# r-2r.net
KiCad netlist of a schematic drawn in EAGLE
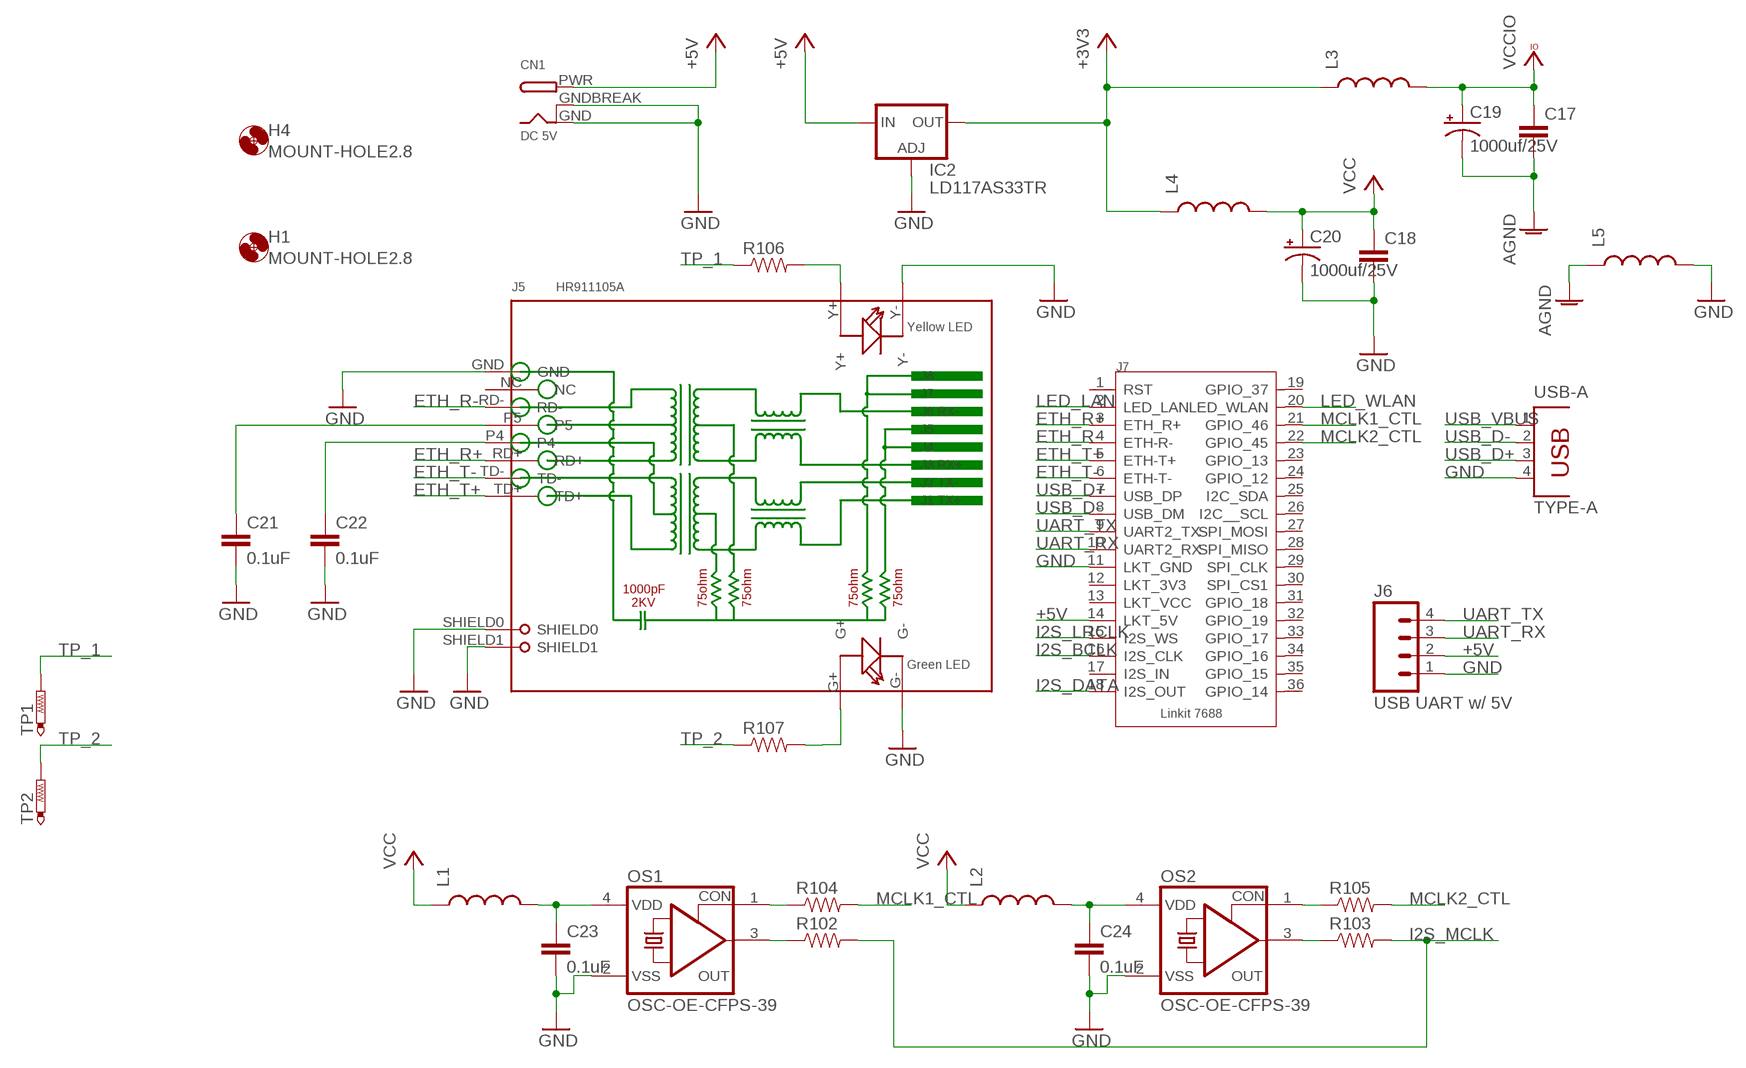
[diagram p0: schematic, sheet 1]
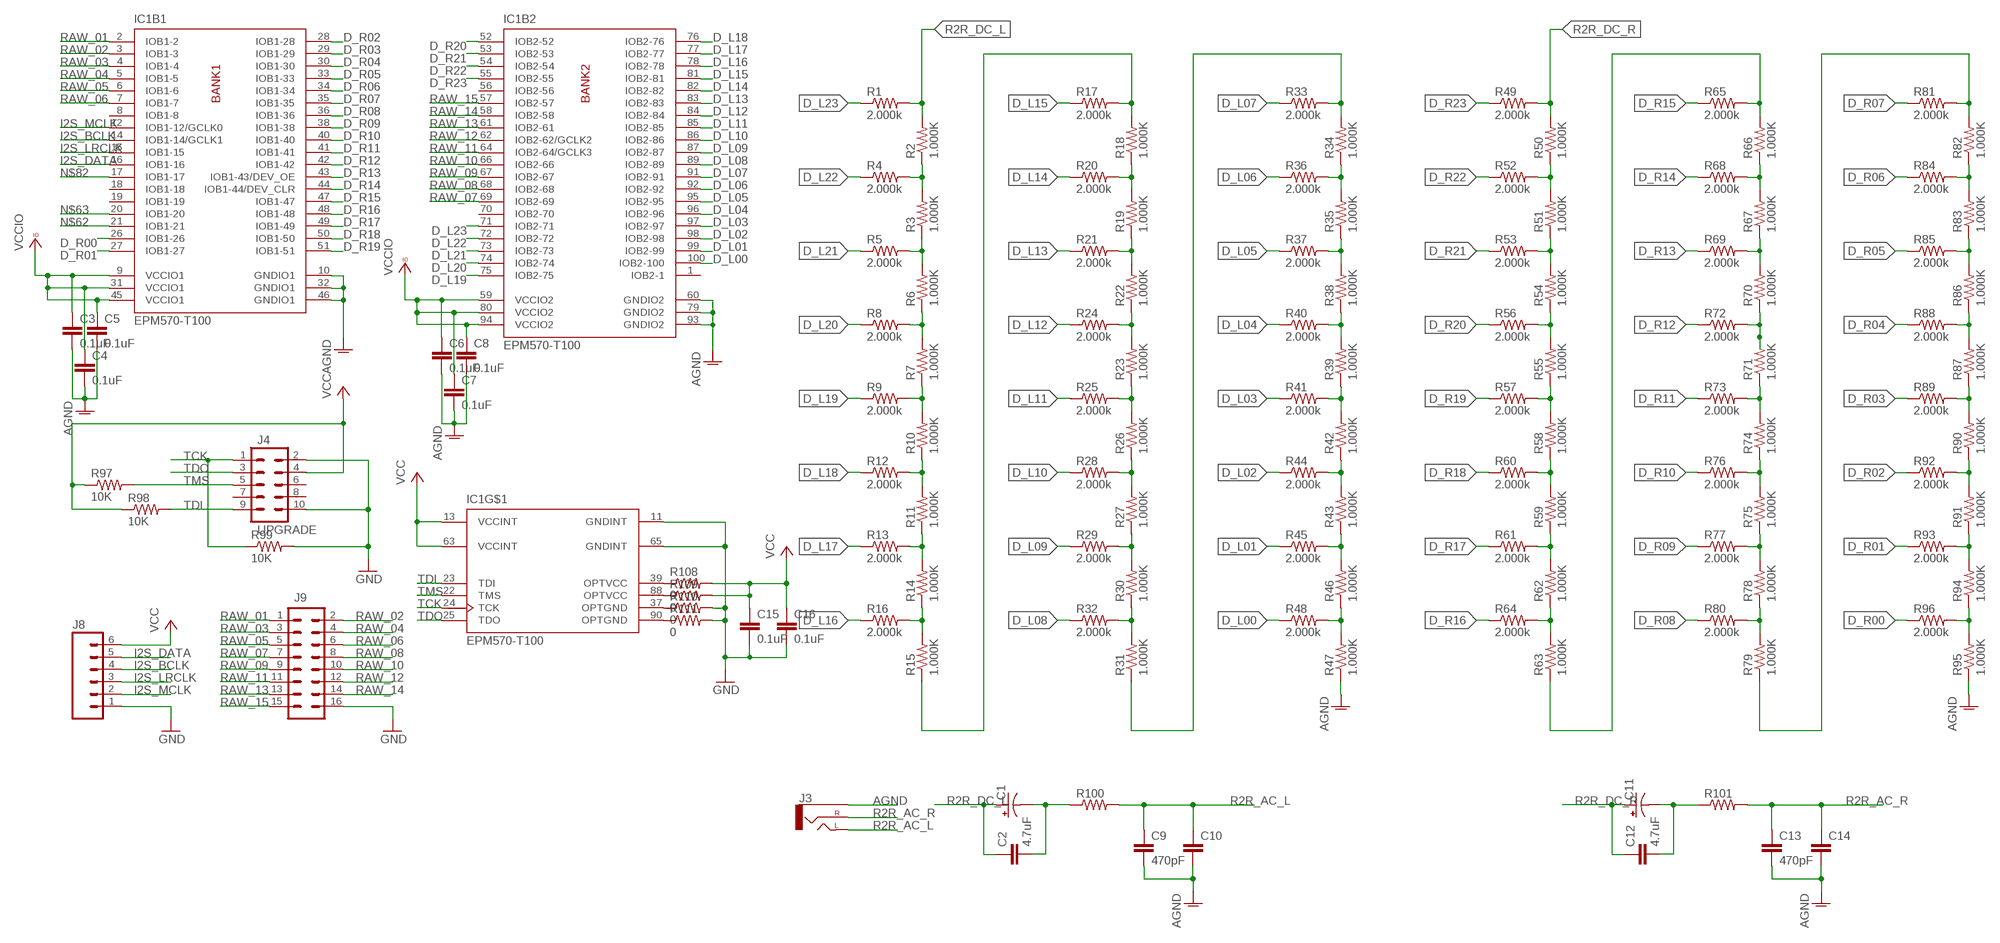
[diagram p1: schematic, sheet 2]

(export (version "E")
  (design (tool "Eeschema 10.0.6"))
  (components
    (comp (ref "C1")
      (value "10UF-25V-20%(PTH)KIT")
      (footprint "eagle-import:CPOL-RADIAL-10UF-25V-KIT")
      (libsource (lib "eagle-import") (part "10UF-25V-20%(PTH)KIT"))
    )
    (comp (ref "C2")
      (value "4.7uF")
      (footprint "eagle-import:1206-CAP")
      (libsource (lib "eagle-import") (part "4.7UF-16V-20%,+80%-(1206)"))
    )
    (comp (ref "C3")
      (value "0.1uF")
      (footprint "eagle-import:0603-CAP")
      (libsource (lib "eagle-import") (part "0.1UF-25V(+80/-20%)(0603)"))
    )
    (comp (ref "C4")
      (value "0.1uF")
      (footprint "eagle-import:0603-CAP")
      (libsource (lib "eagle-import") (part "0.1UF-25V(+80/-20%)(0603)"))
    )
    (comp (ref "C5")
      (value "0.1uF")
      (footprint "eagle-import:0603-CAP")
      (libsource (lib "eagle-import") (part "0.1UF-25V(+80/-20%)(0603)"))
    )
    (comp (ref "C6")
      (value "0.1uF")
      (footprint "eagle-import:0603-CAP")
      (libsource (lib "eagle-import") (part "0.1UF-25V(+80/-20%)(0603)"))
    )
    (comp (ref "C7")
      (value "0.1uF")
      (footprint "eagle-import:0603-CAP")
      (libsource (lib "eagle-import") (part "0.1UF-25V(+80/-20%)(0603)"))
    )
    (comp (ref "C8")
      (value "0.1uF")
      (footprint "eagle-import:0603-CAP")
      (libsource (lib "eagle-import") (part "0.1UF-25V(+80/-20%)(0603)"))
    )
    (comp (ref "C9")
      (value "470pF")
      (footprint "eagle-import:0603-CAP")
      (libsource (lib "eagle-import") (part "470PF-50V-5%(0603)SMD"))
    )
    (comp (ref "C10")
      (value "CAPPTH1")
      (footprint "eagle-import:CAP-PTH-5MM")
      (libsource (lib "eagle-import") (part "CAPPTH1"))
    )
    (comp (ref "C11")
      (value "10UF-25V-20%(PTH)KIT")
      (footprint "eagle-import:CPOL-RADIAL-10UF-25V-KIT")
      (libsource (lib "eagle-import") (part "10UF-25V-20%(PTH)KIT"))
    )
    (comp (ref "C12")
      (value "4.7uF")
      (footprint "eagle-import:1206-CAP")
      (libsource (lib "eagle-import") (part "4.7UF-16V-20%,+80%-(1206)"))
    )
    (comp (ref "C13")
      (value "470pF")
      (footprint "eagle-import:0603-CAP")
      (libsource (lib "eagle-import") (part "470PF-50V-5%(0603)SMD"))
    )
    (comp (ref "C14")
      (value "CAPPTH1")
      (footprint "eagle-import:CAP-PTH-5MM")
      (libsource (lib "eagle-import") (part "CAPPTH1"))
    )
    (comp (ref "C15")
      (value "0.1uF")
      (footprint "eagle-import:0603-CAP")
      (libsource (lib "eagle-import") (part "0.1UF-25V(+80/-20%)(0603)"))
    )
    (comp (ref "C16")
      (value "0.1uF")
      (footprint "eagle-import:0603-CAP")
      (libsource (lib "eagle-import") (part "0.1UF-25V(+80/-20%)(0603)"))
    )
    (comp (ref "IC1")
      (value "EPM570-T100")
      (footprint "eagle-import:TQFP100")
      (libsource (lib "eagle-import") (part "EPM570-T100"))
    )
    (comp (ref "J3")
      (value "AUDIO-JACKSMD2")
      (footprint "eagle-import:AUDIO-JACK-3.5MM-SMD")
      (libsource (lib "eagle-import") (part "AUDIO-JACKSMD2"))
    )
    (comp (ref "J4")
      (value "UPGRADE")
      (footprint "eagle-import:2X5-SHROUDED")
      (libsource (lib "eagle-import") (part "M05X2SHD"))
    )
    (comp (ref "J8")
      (value "M06SILK_FEMALE_PTH")
      (footprint "eagle-import:1X06")
      (libsource (lib "eagle-import") (part "M06SILK_FEMALE_PTH"))
    )
    (comp (ref "J9")
      (value "M08X2")
      (footprint "eagle-import:2X8")
      (libsource (lib "eagle-import") (part "M08X2"))
    )
    (comp (ref "R1")
      (value "2.000k")
      (footprint "eagle-import:0603-RES")
      (libsource (lib "eagle-import") (part "2.0KOHM1/10W5%(0603)"))
    )
    (comp (ref "R2")
      (value "1.000K")
      (footprint "eagle-import:0603-RES")
      (libsource (lib "eagle-import") (part "1KOHM-1/10W-1%(0603)"))
    )
    (comp (ref "R3")
      (value "1.000K")
      (footprint "eagle-import:0603-RES")
      (libsource (lib "eagle-import") (part "1KOHM-1/10W-1%(0603)"))
    )
    (comp (ref "R4")
      (value "2.000k")
      (footprint "eagle-import:0603-RES")
      (libsource (lib "eagle-import") (part "2.0KOHM1/10W5%(0603)"))
    )
    (comp (ref "R5")
      (value "2.000k")
      (footprint "eagle-import:0603-RES")
      (libsource (lib "eagle-import") (part "2.0KOHM1/10W5%(0603)"))
    )
    (comp (ref "R6")
      (value "1.000K")
      (footprint "eagle-import:0603-RES")
      (libsource (lib "eagle-import") (part "1KOHM-1/10W-1%(0603)"))
    )
    (comp (ref "R7")
      (value "1.000K")
      (footprint "eagle-import:0603-RES")
      (libsource (lib "eagle-import") (part "1KOHM-1/10W-1%(0603)"))
    )
    (comp (ref "R8")
      (value "2.000k")
      (footprint "eagle-import:0603-RES")
      (libsource (lib "eagle-import") (part "2.0KOHM1/10W5%(0603)"))
    )
    (comp (ref "R9")
      (value "2.000k")
      (footprint "eagle-import:0603-RES")
      (libsource (lib "eagle-import") (part "2.0KOHM1/10W5%(0603)"))
    )
    (comp (ref "R10")
      (value "1.000K")
      (footprint "eagle-import:0603-RES")
      (libsource (lib "eagle-import") (part "1KOHM-1/10W-1%(0603)"))
    )
    (comp (ref "R11")
      (value "1.000K")
      (footprint "eagle-import:0603-RES")
      (libsource (lib "eagle-import") (part "1KOHM-1/10W-1%(0603)"))
    )
    (comp (ref "R12")
      (value "2.000k")
      (footprint "eagle-import:0603-RES")
      (libsource (lib "eagle-import") (part "2.0KOHM1/10W5%(0603)"))
    )
    (comp (ref "R13")
      (value "2.000k")
      (footprint "eagle-import:0603-RES")
      (libsource (lib "eagle-import") (part "2.0KOHM1/10W5%(0603)"))
    )
    (comp (ref "R14")
      (value "1.000K")
      (footprint "eagle-import:0603-RES")
      (libsource (lib "eagle-import") (part "1KOHM-1/10W-1%(0603)"))
    )
    (comp (ref "R15")
      (value "1.000K")
      (footprint "eagle-import:0603-RES")
      (libsource (lib "eagle-import") (part "1KOHM-1/10W-1%(0603)"))
    )
    (comp (ref "R16")
      (value "2.000k")
      (footprint "eagle-import:0603-RES")
      (libsource (lib "eagle-import") (part "2.0KOHM1/10W5%(0603)"))
    )
    (comp (ref "R17")
      (value "2.000k")
      (footprint "eagle-import:0603-RES")
      (libsource (lib "eagle-import") (part "2.0KOHM1/10W5%(0603)"))
    )
    (comp (ref "R18")
      (value "1.000K")
      (footprint "eagle-import:0603-RES")
      (libsource (lib "eagle-import") (part "1KOHM-1/10W-1%(0603)"))
    )
    (comp (ref "R19")
      (value "1.000K")
      (footprint "eagle-import:0603-RES")
      (libsource (lib "eagle-import") (part "1KOHM-1/10W-1%(0603)"))
    )
    (comp (ref "R20")
      (value "2.000k")
      (footprint "eagle-import:0603-RES")
      (libsource (lib "eagle-import") (part "2.0KOHM1/10W5%(0603)"))
    )
    (comp (ref "R21")
      (value "2.000k")
      (footprint "eagle-import:0603-RES")
      (libsource (lib "eagle-import") (part "2.0KOHM1/10W5%(0603)"))
    )
    (comp (ref "R22")
      (value "1.000K")
      (footprint "eagle-import:0603-RES")
      (libsource (lib "eagle-import") (part "1KOHM-1/10W-1%(0603)"))
    )
    (comp (ref "R23")
      (value "1.000K")
      (footprint "eagle-import:0603-RES")
      (libsource (lib "eagle-import") (part "1KOHM-1/10W-1%(0603)"))
    )
    (comp (ref "R24")
      (value "2.000k")
      (footprint "eagle-import:0603-RES")
      (libsource (lib "eagle-import") (part "2.0KOHM1/10W5%(0603)"))
    )
    (comp (ref "R25")
      (value "2.000k")
      (footprint "eagle-import:0603-RES")
      (libsource (lib "eagle-import") (part "2.0KOHM1/10W5%(0603)"))
    )
    (comp (ref "R26")
      (value "1.000K")
      (footprint "eagle-import:0603-RES")
      (libsource (lib "eagle-import") (part "1KOHM-1/10W-1%(0603)"))
    )
    (comp (ref "R27")
      (value "1.000K")
      (footprint "eagle-import:0603-RES")
      (libsource (lib "eagle-import") (part "1KOHM-1/10W-1%(0603)"))
    )
    (comp (ref "R28")
      (value "2.000k")
      (footprint "eagle-import:0603-RES")
      (libsource (lib "eagle-import") (part "2.0KOHM1/10W5%(0603)"))
    )
    (comp (ref "R29")
      (value "2.000k")
      (footprint "eagle-import:0603-RES")
      (libsource (lib "eagle-import") (part "2.0KOHM1/10W5%(0603)"))
    )
    (comp (ref "R30")
      (value "1.000K")
      (footprint "eagle-import:0603-RES")
      (libsource (lib "eagle-import") (part "1KOHM-1/10W-1%(0603)"))
    )
    (comp (ref "R31")
      (value "1.000K")
      (footprint "eagle-import:0603-RES")
      (libsource (lib "eagle-import") (part "1KOHM-1/10W-1%(0603)"))
    )
    (comp (ref "R32")
      (value "2.000k")
      (footprint "eagle-import:0603-RES")
      (libsource (lib "eagle-import") (part "2.0KOHM1/10W5%(0603)"))
    )
    (comp (ref "R33")
      (value "2.000k")
      (footprint "eagle-import:0603-RES")
      (libsource (lib "eagle-import") (part "2.0KOHM1/10W5%(0603)"))
    )
    (comp (ref "R34")
      (value "1.000K")
      (footprint "eagle-import:0603-RES")
      (libsource (lib "eagle-import") (part "1KOHM-1/10W-1%(0603)"))
    )
    (comp (ref "R35")
      (value "1.000K")
      (footprint "eagle-import:0603-RES")
      (libsource (lib "eagle-import") (part "1KOHM-1/10W-1%(0603)"))
    )
    (comp (ref "R36")
      (value "2.000k")
      (footprint "eagle-import:0603-RES")
      (libsource (lib "eagle-import") (part "2.0KOHM1/10W5%(0603)"))
    )
    (comp (ref "R37")
      (value "2.000k")
      (footprint "eagle-import:0603-RES")
      (libsource (lib "eagle-import") (part "2.0KOHM1/10W5%(0603)"))
    )
    (comp (ref "R38")
      (value "1.000K")
      (footprint "eagle-import:0603-RES")
      (libsource (lib "eagle-import") (part "1KOHM-1/10W-1%(0603)"))
    )
    (comp (ref "R39")
      (value "1.000K")
      (footprint "eagle-import:0603-RES")
      (libsource (lib "eagle-import") (part "1KOHM-1/10W-1%(0603)"))
    )
    (comp (ref "R40")
      (value "2.000k")
      (footprint "eagle-import:0603-RES")
      (libsource (lib "eagle-import") (part "2.0KOHM1/10W5%(0603)"))
    )
    (comp (ref "R41")
      (value "2.000k")
      (footprint "eagle-import:0603-RES")
      (libsource (lib "eagle-import") (part "2.0KOHM1/10W5%(0603)"))
    )
    (comp (ref "R42")
      (value "1.000K")
      (footprint "eagle-import:0603-RES")
      (libsource (lib "eagle-import") (part "1KOHM-1/10W-1%(0603)"))
    )
    (comp (ref "R43")
      (value "1.000K")
      (footprint "eagle-import:0603-RES")
      (libsource (lib "eagle-import") (part "1KOHM-1/10W-1%(0603)"))
    )
    (comp (ref "R44")
      (value "2.000k")
      (footprint "eagle-import:0603-RES")
      (libsource (lib "eagle-import") (part "2.0KOHM1/10W5%(0603)"))
    )
    (comp (ref "R45")
      (value "2.000k")
      (footprint "eagle-import:0603-RES")
      (libsource (lib "eagle-import") (part "2.0KOHM1/10W5%(0603)"))
    )
    (comp (ref "R46")
      (value "1.000K")
      (footprint "eagle-import:0603-RES")
      (libsource (lib "eagle-import") (part "1KOHM-1/10W-1%(0603)"))
    )
    (comp (ref "R47")
      (value "1.000K")
      (footprint "eagle-import:0603-RES")
      (libsource (lib "eagle-import") (part "1KOHM-1/10W-1%(0603)"))
    )
    (comp (ref "R48")
      (value "2.000k")
      (footprint "eagle-import:0603-RES")
      (libsource (lib "eagle-import") (part "2.0KOHM1/10W5%(0603)"))
    )
    (comp (ref "R49")
      (value "2.000k")
      (footprint "eagle-import:0603-RES")
      (libsource (lib "eagle-import") (part "2.0KOHM1/10W5%(0603)"))
    )
    (comp (ref "R50")
      (value "1.000K")
      (footprint "eagle-import:0603-RES")
      (libsource (lib "eagle-import") (part "1KOHM-1/10W-1%(0603)"))
    )
    (comp (ref "R51")
      (value "1.000K")
      (footprint "eagle-import:0603-RES")
      (libsource (lib "eagle-import") (part "1KOHM-1/10W-1%(0603)"))
    )
    (comp (ref "R52")
      (value "2.000k")
      (footprint "eagle-import:0603-RES")
      (libsource (lib "eagle-import") (part "2.0KOHM1/10W5%(0603)"))
    )
    (comp (ref "R53")
      (value "2.000k")
      (footprint "eagle-import:0603-RES")
      (libsource (lib "eagle-import") (part "2.0KOHM1/10W5%(0603)"))
    )
    (comp (ref "R54")
      (value "1.000K")
      (footprint "eagle-import:0603-RES")
      (libsource (lib "eagle-import") (part "1KOHM-1/10W-1%(0603)"))
    )
    (comp (ref "R55")
      (value "1.000K")
      (footprint "eagle-import:0603-RES")
      (libsource (lib "eagle-import") (part "1KOHM-1/10W-1%(0603)"))
    )
    (comp (ref "R56")
      (value "2.000k")
      (footprint "eagle-import:0603-RES")
      (libsource (lib "eagle-import") (part "2.0KOHM1/10W5%(0603)"))
    )
    (comp (ref "R57")
      (value "2.000k")
      (footprint "eagle-import:0603-RES")
      (libsource (lib "eagle-import") (part "2.0KOHM1/10W5%(0603)"))
    )
    (comp (ref "R58")
      (value "1.000K")
      (footprint "eagle-import:0603-RES")
      (libsource (lib "eagle-import") (part "1KOHM-1/10W-1%(0603)"))
    )
    (comp (ref "R59")
      (value "1.000K")
      (footprint "eagle-import:0603-RES")
      (libsource (lib "eagle-import") (part "1KOHM-1/10W-1%(0603)"))
    )
    (comp (ref "R60")
      (value "2.000k")
      (footprint "eagle-import:0603-RES")
      (libsource (lib "eagle-import") (part "2.0KOHM1/10W5%(0603)"))
    )
    (comp (ref "R61")
      (value "2.000k")
      (footprint "eagle-import:0603-RES")
      (libsource (lib "eagle-import") (part "2.0KOHM1/10W5%(0603)"))
    )
    (comp (ref "R62")
      (value "1.000K")
      (footprint "eagle-import:0603-RES")
      (libsource (lib "eagle-import") (part "1KOHM-1/10W-1%(0603)"))
    )
    (comp (ref "R63")
      (value "1.000K")
      (footprint "eagle-import:0603-RES")
      (libsource (lib "eagle-import") (part "1KOHM-1/10W-1%(0603)"))
    )
    (comp (ref "R64")
      (value "2.000k")
      (footprint "eagle-import:0603-RES")
      (libsource (lib "eagle-import") (part "2.0KOHM1/10W5%(0603)"))
    )
    (comp (ref "R65")
      (value "2.000k")
      (footprint "eagle-import:0603-RES")
      (libsource (lib "eagle-import") (part "2.0KOHM1/10W5%(0603)"))
    )
    (comp (ref "R66")
      (value "1.000K")
      (footprint "eagle-import:0603-RES")
      (libsource (lib "eagle-import") (part "1KOHM-1/10W-1%(0603)"))
    )
    (comp (ref "R67")
      (value "1.000K")
      (footprint "eagle-import:0603-RES")
      (libsource (lib "eagle-import") (part "1KOHM-1/10W-1%(0603)"))
    )
    (comp (ref "R68")
      (value "2.000k")
      (footprint "eagle-import:0603-RES")
      (libsource (lib "eagle-import") (part "2.0KOHM1/10W5%(0603)"))
    )
    (comp (ref "R69")
      (value "2.000k")
      (footprint "eagle-import:0603-RES")
      (libsource (lib "eagle-import") (part "2.0KOHM1/10W5%(0603)"))
    )
    (comp (ref "R70")
      (value "1.000K")
      (footprint "eagle-import:0603-RES")
      (libsource (lib "eagle-import") (part "1KOHM-1/10W-1%(0603)"))
    )
    (comp (ref "R71")
      (value "1.000K")
      (footprint "eagle-import:0603-RES")
      (libsource (lib "eagle-import") (part "1KOHM-1/10W-1%(0603)"))
    )
    (comp (ref "R72")
      (value "2.000k")
      (footprint "eagle-import:0603-RES")
      (libsource (lib "eagle-import") (part "2.0KOHM1/10W5%(0603)"))
    )
    (comp (ref "R73")
      (value "2.000k")
      (footprint "eagle-import:0603-RES")
      (libsource (lib "eagle-import") (part "2.0KOHM1/10W5%(0603)"))
    )
    (comp (ref "R74")
      (value "1.000K")
      (footprint "eagle-import:0603-RES")
      (libsource (lib "eagle-import") (part "1KOHM-1/10W-1%(0603)"))
    )
    (comp (ref "R75")
      (value "1.000K")
      (footprint "eagle-import:0603-RES")
      (libsource (lib "eagle-import") (part "1KOHM-1/10W-1%(0603)"))
    )
    (comp (ref "R76")
      (value "2.000k")
      (footprint "eagle-import:0603-RES")
      (libsource (lib "eagle-import") (part "2.0KOHM1/10W5%(0603)"))
    )
    (comp (ref "R77")
      (value "2.000k")
      (footprint "eagle-import:0603-RES")
      (libsource (lib "eagle-import") (part "2.0KOHM1/10W5%(0603)"))
    )
    (comp (ref "R78")
      (value "1.000K")
      (footprint "eagle-import:0603-RES")
      (libsource (lib "eagle-import") (part "1KOHM-1/10W-1%(0603)"))
    )
    (comp (ref "R79")
      (value "1.000K")
      (footprint "eagle-import:0603-RES")
      (libsource (lib "eagle-import") (part "1KOHM-1/10W-1%(0603)"))
    )
    (comp (ref "R80")
      (value "2.000k")
      (footprint "eagle-import:0603-RES")
      (libsource (lib "eagle-import") (part "2.0KOHM1/10W5%(0603)"))
    )
    (comp (ref "R81")
      (value "2.000k")
      (footprint "eagle-import:0603-RES")
      (libsource (lib "eagle-import") (part "2.0KOHM1/10W5%(0603)"))
    )
    (comp (ref "R82")
      (value "1.000K")
      (footprint "eagle-import:0603-RES")
      (libsource (lib "eagle-import") (part "1KOHM-1/10W-1%(0603)"))
    )
    (comp (ref "R83")
      (value "1.000K")
      (footprint "eagle-import:0603-RES")
      (libsource (lib "eagle-import") (part "1KOHM-1/10W-1%(0603)"))
    )
    (comp (ref "R84")
      (value "2.000k")
      (footprint "eagle-import:0603-RES")
      (libsource (lib "eagle-import") (part "2.0KOHM1/10W5%(0603)"))
    )
    (comp (ref "R85")
      (value "2.000k")
      (footprint "eagle-import:0603-RES")
      (libsource (lib "eagle-import") (part "2.0KOHM1/10W5%(0603)"))
    )
    (comp (ref "R86")
      (value "1.000K")
      (footprint "eagle-import:0603-RES")
      (libsource (lib "eagle-import") (part "1KOHM-1/10W-1%(0603)"))
    )
    (comp (ref "R87")
      (value "1.000K")
      (footprint "eagle-import:0603-RES")
      (libsource (lib "eagle-import") (part "1KOHM-1/10W-1%(0603)"))
    )
    (comp (ref "R88")
      (value "2.000k")
      (footprint "eagle-import:0603-RES")
      (libsource (lib "eagle-import") (part "2.0KOHM1/10W5%(0603)"))
    )
    (comp (ref "R89")
      (value "2.000k")
      (footprint "eagle-import:0603-RES")
      (libsource (lib "eagle-import") (part "2.0KOHM1/10W5%(0603)"))
    )
    (comp (ref "R90")
      (value "1.000K")
      (footprint "eagle-import:0603-RES")
      (libsource (lib "eagle-import") (part "1KOHM-1/10W-1%(0603)"))
    )
    (comp (ref "R91")
      (value "1.000K")
      (footprint "eagle-import:0603-RES")
      (libsource (lib "eagle-import") (part "1KOHM-1/10W-1%(0603)"))
    )
    (comp (ref "R92")
      (value "2.000k")
      (footprint "eagle-import:0603-RES")
      (libsource (lib "eagle-import") (part "2.0KOHM1/10W5%(0603)"))
    )
    (comp (ref "R93")
      (value "2.000k")
      (footprint "eagle-import:0603-RES")
      (libsource (lib "eagle-import") (part "2.0KOHM1/10W5%(0603)"))
    )
    (comp (ref "R94")
      (value "1.000K")
      (footprint "eagle-import:0603-RES")
      (libsource (lib "eagle-import") (part "1KOHM-1/10W-1%(0603)"))
    )
    (comp (ref "R95")
      (value "1.000K")
      (footprint "eagle-import:0603-RES")
      (libsource (lib "eagle-import") (part "1KOHM-1/10W-1%(0603)"))
    )
    (comp (ref "R96")
      (value "2.000k")
      (footprint "eagle-import:0603-RES")
      (libsource (lib "eagle-import") (part "2.0KOHM1/10W5%(0603)"))
    )
    (comp (ref "R97")
      (value "10K")
      (footprint "eagle-import:0603-RES")
      (libsource (lib "eagle-import") (part "10OHM-1/10W-5%0603SMD"))
    )
    (comp (ref "R98")
      (value "10K")
      (footprint "eagle-import:0603-RES")
      (libsource (lib "eagle-import") (part "10OHM-1/10W-5%0603SMD"))
    )
    (comp (ref "R99")
      (value "10K")
      (footprint "eagle-import:0603-RES")
      (libsource (lib "eagle-import") (part "10OHM-1/10W-5%0603SMD"))
    )
    (comp (ref "R100")
      (value "RESISTOR1206")
      (footprint "eagle-import:1206")
      (libsource (lib "eagle-import") (part "SparkFun-Resistors_RESISTOR1206"))
    )
    (comp (ref "R101")
      (value "RESISTOR1206")
      (footprint "eagle-import:1206")
      (libsource (lib "eagle-import") (part "SparkFun-Resistors_RESISTOR1206"))
    )
    (comp (ref "R108")
      (value "0")
      (footprint "eagle-import:0603")
      (libsource (lib "eagle-import") (part "0OHM-1/10W-5%(0603)"))
    )
    (comp (ref "R109")
      (value "0")
      (footprint "eagle-import:0603")
      (libsource (lib "eagle-import") (part "0OHM-1/10W-5%(0603)"))
    )
    (comp (ref "R110")
      (value "0")
      (footprint "eagle-import:0603")
      (libsource (lib "eagle-import") (part "0OHM-1/10W-5%(0603)"))
    )
    (comp (ref "R111")
      (value "0")
      (footprint "eagle-import:0603")
      (libsource (lib "eagle-import") (part "0OHM-1/10W-5%(0603)"))
    )
    (comp (ref "C17")
      (value "CAPPTH1")
      (footprint "eagle-import:CAP-PTH-5MM")
      (libsource (lib "eagle-import") (part "CAPPTH1"))
    )
    (comp (ref "C18")
      (value "CAPPTH1")
      (footprint "eagle-import:CAP-PTH-5MM")
      (libsource (lib "eagle-import") (part "CAPPTH1"))
    )
    (comp (ref "C19")
      (value "1000uf/25V")
      (footprint "eagle-import:CPOL-RADIAL-1000UF-25V-KIT")
      (libsource (lib "eagle-import") (part "1000UF-25V(PTH)KIT"))
    )
    (comp (ref "C20")
      (value "1000uf/25V")
      (footprint "eagle-import:CPOL-RADIAL-1000UF-25V-KIT")
      (libsource (lib "eagle-import") (part "1000UF-25V(PTH)KIT"))
    )
    (comp (ref "C21")
      (value "0.1uF")
      (footprint "eagle-import:0603-CAP")
      (libsource (lib "eagle-import") (part "0.1UF-25V(+80/-20%)(0603)"))
    )
    (comp (ref "C22")
      (value "0.1uF")
      (footprint "eagle-import:0603-CAP")
      (libsource (lib "eagle-import") (part "0.1UF-25V(+80/-20%)(0603)"))
    )
    (comp (ref "C23")
      (value "0.1uF")
      (footprint "eagle-import:0603-CAP")
      (libsource (lib "eagle-import") (part "0.1UF-25V(+80/-20%)(0603)"))
    )
    (comp (ref "C24")
      (value "0.1uF")
      (footprint "eagle-import:0603-CAP")
      (libsource (lib "eagle-import") (part "0.1UF-25V(+80/-20%)(0603)"))
    )
    (comp (ref "CN1")
      (value "DC 5V")
      (footprint "eagle-import:DCJACK_2MM_PTH")
      (libsource (lib "eagle-import") (part "DCBARRELPTH"))
    )
    (comp (ref "H1")
      (value "MOUNT-HOLE2.8")
      (footprint "eagle-import:2,8")
      (libsource (lib "eagle-import") (part "MOUNT-HOLE2.8"))
    )
    (comp (ref "H4")
      (value "MOUNT-HOLE2.8")
      (footprint "eagle-import:2,8")
      (libsource (lib "eagle-import") (part "MOUNT-HOLE2.8"))
    )
    (comp (ref "IC2")
      (value "LD117AS33TR")
      (footprint "eagle-import:SOT223")
      (libsource (lib "eagle-import") (part "LD117A?S33TR"))
    )
    (comp (ref "J5")
      (value "HR911105A")
      (footprint "eagle-import:RJ45-12+2P-21.3X16.04X13.4MM")
      (libsource (lib "eagle-import") (part "DIP-RJ45-CONNECTOR(HR911105A)"))
    )
    (comp (ref "J6")
      (value "USB UART w/ 5V")
      (footprint "eagle-import:1X04")
      (libsource (lib "eagle-import") (part "M04PTH"))
    )
    (comp (ref "J7")
      (value "LINKIT-7688")
      (footprint "eagle-import:LINKIT-7688-2X18")
      (libsource (lib "eagle-import") (part "LINKIT-7688"))
    )
    (comp (ref "L1")
      (value "INDUCTOR0603")
      (footprint "eagle-import:0603")
      (libsource (lib "eagle-import") (part "INDUCTOR0603"))
    )
    (comp (ref "L2")
      (value "INDUCTOR0603")
      (footprint "eagle-import:0603")
      (libsource (lib "eagle-import") (part "INDUCTOR0603"))
    )
    (comp (ref "L3")
      (value "INDUCTORAXIAL-0.6")
      (footprint "eagle-import:AXIAL-0.6")
      (libsource (lib "eagle-import") (part "INDUCTORAXIAL-0.6"))
    )
    (comp (ref "L4")
      (value "INDUCTORAXIAL-0.6")
      (footprint "eagle-import:AXIAL-0.6")
      (libsource (lib "eagle-import") (part "INDUCTORAXIAL-0.6"))
    )
    (comp (ref "L5")
      (value "INDUCTOR0603")
      (footprint "eagle-import:0603")
      (libsource (lib "eagle-import") (part "INDUCTOR0603"))
    )
    (comp (ref "OS1")
      (value "OSC-OE-CFPS-39")
      (footprint "eagle-import:3.4X2.7-4-PAD")
      (libsource (lib "eagle-import") (part "OSC-OE-CFPS-39"))
    )
    (comp (ref "OS2")
      (value "OSC-OE-CFPS-39")
      (footprint "eagle-import:3.4X2.7-4-PAD")
      (libsource (lib "eagle-import") (part "OSC-OE-CFPS-39"))
    )
    (comp (ref "R102")
      (value "RESISTOR0603-RES")
      (footprint "eagle-import:0603-RES")
      (libsource (lib "eagle-import") (part "RESISTOR0603-RES"))
    )
    (comp (ref "R103")
      (value "RESISTOR0603-RES")
      (footprint "eagle-import:0603-RES")
      (libsource (lib "eagle-import") (part "RESISTOR0603-RES"))
    )
    (comp (ref "R104")
      (value "RESISTOR0603-RES")
      (footprint "eagle-import:0603-RES")
      (libsource (lib "eagle-import") (part "RESISTOR0603-RES"))
    )
    (comp (ref "R105")
      (value "RESISTOR0603-RES")
      (footprint "eagle-import:0603-RES")
      (libsource (lib "eagle-import") (part "RESISTOR0603-RES"))
    )
    (comp (ref "R106")
      (value "RESISTOR0603-RES")
      (footprint "eagle-import:0603-RES")
      (libsource (lib "eagle-import") (part "RESISTOR0603-RES"))
    )
    (comp (ref "R107")
      (value "RESISTOR0603-RES")
      (footprint "eagle-import:0603-RES")
      (libsource (lib "eagle-import") (part "RESISTOR0603-RES"))
    )
    (comp (ref "TP1")
      (value "PTR1PAD1-13")
      (footprint "eagle-import:P1-13")
      (libsource (lib "eagle-import") (part "PTR1PAD1-13"))
    )
    (comp (ref "TP2")
      (value "PTR1PAD1-13")
      (footprint "eagle-import:P1-13")
      (libsource (lib "eagle-import") (part "PTR1PAD1-13"))
    )
    (comp (ref "USB-A")
      (value "TYPE-A")
      (footprint "eagle-import:PN87520")
      (libsource (lib "eagle-import") (part "PN87520"))
    )
  )
  (nets
    (net (code "1") (name "+3V3") (class "Default")
      (node (ref "IC2") (pin "4") (pinfunction "OUT_4") (pintype "passive"))
      (node (ref "L3") (pin "P$1") (pinfunction "1_P$1") (pintype "passive"))
      (node (ref "L4") (pin "P$1") (pinfunction "1_P$1") (pintype "passive"))
    )
    (net (code "2") (name "+5V") (class "Default")
      (node (ref "CN1") (pin "PWR") (pinfunction "PWR_PWR") (pintype "power_in"))
      (node (ref "IC2") (pin "3") (pinfunction "IN_3") (pintype "input"))
      (node (ref "J6") (pin "2") (pinfunction "2_2") (pintype "passive"))
      (node (ref "J7") (pin "14") (pinfunction "LKT_5V_14") (pintype "bidirectional"))
    )
    (net (code "3") (name "AGND") (class "Default")
      (node (ref "C10") (pin "2") (pinfunction "2_2") (pintype "passive"))
      (node (ref "C13") (pin "2") (pinfunction "2_2") (pintype "passive"))
      (node (ref "C14") (pin "2") (pinfunction "2_2") (pintype "passive"))
      (node (ref "C17") (pin "2") (pinfunction "2_2") (pintype "passive"))
      (node (ref "C19") (pin "-") (pinfunction "-_-") (pintype "passive"))
      (node (ref "C3") (pin "2") (pinfunction "2_2") (pintype "passive"))
      (node (ref "C4") (pin "2") (pinfunction "2_2") (pintype "passive"))
      (node (ref "C5") (pin "2") (pinfunction "2_2") (pintype "passive"))
      (node (ref "C6") (pin "2") (pinfunction "2_2") (pintype "passive"))
      (node (ref "C7") (pin "2") (pinfunction "2_2") (pintype "passive"))
      (node (ref "C8") (pin "2") (pinfunction "2_2") (pintype "passive"))
      (node (ref "C9") (pin "2") (pinfunction "2_2") (pintype "passive"))
      (node (ref "IC1") (pin "10") (pinfunction "GNDIO1_10") (pintype "power_in"))
      (node (ref "IC1") (pin "32") (pinfunction "GNDIO1_32") (pintype "power_in"))
      (node (ref "IC1") (pin "46") (pinfunction "GNDIO1_46") (pintype "power_in"))
      (node (ref "IC1") (pin "60") (pinfunction "GNDIO2_60") (pintype "power_in"))
      (node (ref "IC1") (pin "79") (pinfunction "GNDIO2_79") (pintype "power_in"))
      (node (ref "IC1") (pin "93") (pinfunction "GNDIO2_93") (pintype "power_in"))
      (node (ref "J3") (pin "SLEEVE") (pinfunction "SLEEVE_SLEEVE") (pintype "bidirectional"))
      (node (ref "L5") (pin "1") (pinfunction "1_1") (pintype "passive"))
      (node (ref "R47") (pin "1") (pinfunction "1_1") (pintype "passive"))
      (node (ref "R95") (pin "1") (pinfunction "1_1") (pintype "passive"))
    )
    (net (code "4") (name "D_L00") (class "Default")
      (node (ref "IC1") (pin "100") (pinfunction "IOB2-100_100") (pintype "bidirectional"))
      (node (ref "R48") (pin "1") (pinfunction "1_1") (pintype "passive"))
    )
    (net (code "5") (name "D_L01") (class "Default")
      (node (ref "IC1") (pin "99") (pinfunction "IOB2-99_99") (pintype "bidirectional"))
      (node (ref "R45") (pin "1") (pinfunction "1_1") (pintype "passive"))
    )
    (net (code "6") (name "D_L02") (class "Default")
      (node (ref "IC1") (pin "98") (pinfunction "IOB2-98_98") (pintype "bidirectional"))
      (node (ref "R44") (pin "1") (pinfunction "1_1") (pintype "passive"))
    )
    (net (code "7") (name "D_L03") (class "Default")
      (node (ref "IC1") (pin "97") (pinfunction "IOB2-97_97") (pintype "bidirectional"))
      (node (ref "R41") (pin "1") (pinfunction "1_1") (pintype "passive"))
    )
    (net (code "8") (name "D_L04") (class "Default")
      (node (ref "IC1") (pin "96") (pinfunction "IOB2-96_96") (pintype "bidirectional"))
      (node (ref "R40") (pin "1") (pinfunction "1_1") (pintype "passive"))
    )
    (net (code "9") (name "D_L05") (class "Default")
      (node (ref "IC1") (pin "95") (pinfunction "IOB2-95_95") (pintype "bidirectional"))
      (node (ref "R37") (pin "1") (pinfunction "1_1") (pintype "passive"))
    )
    (net (code "10") (name "D_L06") (class "Default")
      (node (ref "IC1") (pin "92") (pinfunction "IOB2-92_92") (pintype "bidirectional"))
      (node (ref "R36") (pin "1") (pinfunction "1_1") (pintype "passive"))
    )
    (net (code "11") (name "D_L07") (class "Default")
      (node (ref "IC1") (pin "91") (pinfunction "IOB2-91_91") (pintype "bidirectional"))
      (node (ref "R33") (pin "1") (pinfunction "1_1") (pintype "passive"))
    )
    (net (code "12") (name "D_L08") (class "Default")
      (node (ref "IC1") (pin "89") (pinfunction "IOB2-89_89") (pintype "bidirectional"))
      (node (ref "R32") (pin "1") (pinfunction "1_1") (pintype "passive"))
    )
    (net (code "13") (name "D_L09") (class "Default")
      (node (ref "IC1") (pin "87") (pinfunction "IOB2-87_87") (pintype "bidirectional"))
      (node (ref "R29") (pin "1") (pinfunction "1_1") (pintype "passive"))
    )
    (net (code "14") (name "D_L10") (class "Default")
      (node (ref "IC1") (pin "86") (pinfunction "IOB2-86_86") (pintype "bidirectional"))
      (node (ref "R28") (pin "1") (pinfunction "1_1") (pintype "passive"))
    )
    (net (code "15") (name "D_L11") (class "Default")
      (node (ref "IC1") (pin "85") (pinfunction "IOB2-85_85") (pintype "bidirectional"))
      (node (ref "R25") (pin "1") (pinfunction "1_1") (pintype "passive"))
    )
    (net (code "16") (name "D_L12") (class "Default")
      (node (ref "IC1") (pin "84") (pinfunction "IOB2-84_84") (pintype "bidirectional"))
      (node (ref "R24") (pin "1") (pinfunction "1_1") (pintype "passive"))
    )
    (net (code "17") (name "D_L13") (class "Default")
      (node (ref "IC1") (pin "83") (pinfunction "IOB2-83_83") (pintype "bidirectional"))
      (node (ref "R21") (pin "1") (pinfunction "1_1") (pintype "passive"))
    )
    (net (code "18") (name "D_L14") (class "Default")
      (node (ref "IC1") (pin "82") (pinfunction "IOB2-82_82") (pintype "bidirectional"))
      (node (ref "R20") (pin "1") (pinfunction "1_1") (pintype "passive"))
    )
    (net (code "19") (name "D_L15") (class "Default")
      (node (ref "IC1") (pin "81") (pinfunction "IOB2-81_81") (pintype "bidirectional"))
      (node (ref "R17") (pin "1") (pinfunction "1_1") (pintype "passive"))
    )
    (net (code "20") (name "D_L16") (class "Default")
      (node (ref "IC1") (pin "78") (pinfunction "IOB2-78_78") (pintype "bidirectional"))
      (node (ref "R16") (pin "1") (pinfunction "1_1") (pintype "passive"))
    )
    (net (code "21") (name "D_L17") (class "Default")
      (node (ref "IC1") (pin "77") (pinfunction "IOB2-77_77") (pintype "bidirectional"))
      (node (ref "R13") (pin "1") (pinfunction "1_1") (pintype "passive"))
    )
    (net (code "22") (name "D_L18") (class "Default")
      (node (ref "IC1") (pin "76") (pinfunction "IOB2-76_76") (pintype "bidirectional"))
      (node (ref "R12") (pin "1") (pinfunction "1_1") (pintype "passive"))
    )
    (net (code "23") (name "D_L19") (class "Default")
      (node (ref "IC1") (pin "75") (pinfunction "IOB2-75_75") (pintype "bidirectional"))
      (node (ref "R9") (pin "1") (pinfunction "1_1") (pintype "passive"))
    )
    (net (code "24") (name "D_L20") (class "Default")
      (node (ref "IC1") (pin "74") (pinfunction "IOB2-74_74") (pintype "bidirectional"))
      (node (ref "R8") (pin "1") (pinfunction "1_1") (pintype "passive"))
    )
    (net (code "25") (name "D_L21") (class "Default")
      (node (ref "IC1") (pin "73") (pinfunction "IOB2-73_73") (pintype "bidirectional"))
      (node (ref "R5") (pin "1") (pinfunction "1_1") (pintype "passive"))
    )
    (net (code "26") (name "D_L22") (class "Default")
      (node (ref "IC1") (pin "72") (pinfunction "IOB2-72_72") (pintype "bidirectional"))
      (node (ref "R4") (pin "1") (pinfunction "1_1") (pintype "passive"))
    )
    (net (code "27") (name "D_L23") (class "Default")
      (node (ref "IC1") (pin "71") (pinfunction "IOB2-71_71") (pintype "bidirectional"))
      (node (ref "R1") (pin "1") (pinfunction "1_1") (pintype "passive"))
    )
    (net (code "28") (name "D_R00") (class "Default")
      (node (ref "IC1") (pin "26") (pinfunction "IOB1-26_26") (pintype "bidirectional"))
      (node (ref "R96") (pin "1") (pinfunction "1_1") (pintype "passive"))
    )
    (net (code "29") (name "D_R01") (class "Default")
      (node (ref "IC1") (pin "27") (pinfunction "IOB1-27_27") (pintype "bidirectional"))
      (node (ref "R93") (pin "1") (pinfunction "1_1") (pintype "passive"))
    )
    (net (code "30") (name "D_R02") (class "Default")
      (node (ref "IC1") (pin "28") (pinfunction "IOB1-28_28") (pintype "bidirectional"))
      (node (ref "R92") (pin "1") (pinfunction "1_1") (pintype "passive"))
    )
    (net (code "31") (name "D_R03") (class "Default")
      (node (ref "IC1") (pin "29") (pinfunction "IOB1-29_29") (pintype "bidirectional"))
      (node (ref "R89") (pin "1") (pinfunction "1_1") (pintype "passive"))
    )
    (net (code "32") (name "D_R04") (class "Default")
      (node (ref "IC1") (pin "30") (pinfunction "IOB1-30_30") (pintype "bidirectional"))
      (node (ref "R88") (pin "1") (pinfunction "1_1") (pintype "passive"))
    )
    (net (code "33") (name "D_R05") (class "Default")
      (node (ref "IC1") (pin "33") (pinfunction "IOB1-33_33") (pintype "bidirectional"))
      (node (ref "R85") (pin "1") (pinfunction "1_1") (pintype "passive"))
    )
    (net (code "34") (name "D_R06") (class "Default")
      (node (ref "IC1") (pin "34") (pinfunction "IOB1-34_34") (pintype "bidirectional"))
      (node (ref "R84") (pin "1") (pinfunction "1_1") (pintype "passive"))
    )
    (net (code "35") (name "D_R07") (class "Default")
      (node (ref "IC1") (pin "35") (pinfunction "IOB1-35_35") (pintype "bidirectional"))
      (node (ref "R81") (pin "1") (pinfunction "1_1") (pintype "passive"))
    )
    (net (code "36") (name "D_R08") (class "Default")
      (node (ref "IC1") (pin "36") (pinfunction "IOB1-36_36") (pintype "bidirectional"))
      (node (ref "R80") (pin "1") (pinfunction "1_1") (pintype "passive"))
    )
    (net (code "37") (name "D_R09") (class "Default")
      (node (ref "IC1") (pin "38") (pinfunction "IOB1-38_38") (pintype "bidirectional"))
      (node (ref "R77") (pin "1") (pinfunction "1_1") (pintype "passive"))
    )
    (net (code "38") (name "D_R10") (class "Default")
      (node (ref "IC1") (pin "40") (pinfunction "IOB1-40_40") (pintype "bidirectional"))
      (node (ref "R76") (pin "1") (pinfunction "1_1") (pintype "passive"))
    )
    (net (code "39") (name "D_R11") (class "Default")
      (node (ref "IC1") (pin "41") (pinfunction "IOB1-41_41") (pintype "bidirectional"))
      (node (ref "R73") (pin "1") (pinfunction "1_1") (pintype "passive"))
    )
    (net (code "40") (name "D_R12") (class "Default")
      (node (ref "IC1") (pin "42") (pinfunction "IOB1-42_42") (pintype "bidirectional"))
      (node (ref "R72") (pin "1") (pinfunction "1_1") (pintype "passive"))
    )
    (net (code "41") (name "D_R13") (class "Default")
      (node (ref "IC1") (pin "43") (pinfunction "IOB1-43/DEV_OE_43") (pintype "bidirectional"))
      (node (ref "R69") (pin "1") (pinfunction "1_1") (pintype "passive"))
    )
    (net (code "42") (name "D_R14") (class "Default")
      (node (ref "IC1") (pin "44") (pinfunction "IOB1-44/DEV_CLR_44") (pintype "bidirectional"))
      (node (ref "R68") (pin "1") (pinfunction "1_1") (pintype "passive"))
    )
    (net (code "43") (name "D_R15") (class "Default")
      (node (ref "IC1") (pin "47") (pinfunction "IOB1-47_47") (pintype "bidirectional"))
      (node (ref "R65") (pin "1") (pinfunction "1_1") (pintype "passive"))
    )
    (net (code "44") (name "D_R16") (class "Default")
      (node (ref "IC1") (pin "48") (pinfunction "IOB1-48_48") (pintype "bidirectional"))
      (node (ref "R64") (pin "1") (pinfunction "1_1") (pintype "passive"))
    )
    (net (code "45") (name "D_R17") (class "Default")
      (node (ref "IC1") (pin "49") (pinfunction "IOB1-49_49") (pintype "bidirectional"))
      (node (ref "R61") (pin "1") (pinfunction "1_1") (pintype "passive"))
    )
    (net (code "46") (name "D_R18") (class "Default")
      (node (ref "IC1") (pin "50") (pinfunction "IOB1-50_50") (pintype "bidirectional"))
      (node (ref "R60") (pin "1") (pinfunction "1_1") (pintype "passive"))
    )
    (net (code "47") (name "D_R19") (class "Default")
      (node (ref "IC1") (pin "51") (pinfunction "IOB1-51_51") (pintype "bidirectional"))
      (node (ref "R57") (pin "1") (pinfunction "1_1") (pintype "passive"))
    )
    (net (code "48") (name "D_R20") (class "Default")
      (node (ref "IC1") (pin "52") (pinfunction "IOB2-52_52") (pintype "bidirectional"))
      (node (ref "R56") (pin "1") (pinfunction "1_1") (pintype "passive"))
    )
    (net (code "49") (name "D_R21") (class "Default")
      (node (ref "IC1") (pin "53") (pinfunction "IOB2-53_53") (pintype "bidirectional"))
      (node (ref "R53") (pin "1") (pinfunction "1_1") (pintype "passive"))
    )
    (net (code "50") (name "D_R22") (class "Default")
      (node (ref "IC1") (pin "54") (pinfunction "IOB2-54_54") (pintype "bidirectional"))
      (node (ref "R52") (pin "1") (pinfunction "1_1") (pintype "passive"))
    )
    (net (code "51") (name "D_R23") (class "Default")
      (node (ref "IC1") (pin "55") (pinfunction "IOB2-55_55") (pintype "bidirectional"))
      (node (ref "R49") (pin "1") (pinfunction "1_1") (pintype "passive"))
    )
    (net (code "52") (name "ETH_R+") (class "Default")
      (node (ref "J5") (pin "RD+") (pinfunction "RD+_RD+") (pintype "bidirectional"))
      (node (ref "J7") (pin "3") (pinfunction "ETH_R+_3") (pintype "bidirectional"))
    )
    (net (code "53") (name "ETH_R-") (class "Default")
      (node (ref "J5") (pin "RD-") (pinfunction "RD-_RD-") (pintype "bidirectional"))
      (node (ref "J7") (pin "4") (pinfunction "ETH-R-_4") (pintype "bidirectional"))
    )
    (net (code "54") (name "ETH_T+") (class "Default")
      (node (ref "J5") (pin "TD+") (pinfunction "TD+_TD+") (pintype "bidirectional"))
      (node (ref "J7") (pin "5") (pinfunction "ETH-T+_5") (pintype "bidirectional"))
    )
    (net (code "55") (name "ETH_T-") (class "Default")
      (node (ref "J5") (pin "TD-") (pinfunction "TD-_TD-") (pintype "bidirectional"))
      (node (ref "J7") (pin "6") (pinfunction "ETH-T-_6") (pintype "bidirectional"))
    )
    (net (code "56") (name "GND") (class "Default")
      (node (ref "C15") (pin "2") (pinfunction "2_2") (pintype "passive"))
      (node (ref "C16") (pin "2") (pinfunction "2_2") (pintype "passive"))
      (node (ref "C18") (pin "2") (pinfunction "2_2") (pintype "passive"))
      (node (ref "C20") (pin "-") (pinfunction "-_-") (pintype "passive"))
      (node (ref "C21") (pin "2") (pinfunction "2_2") (pintype "passive"))
      (node (ref "C22") (pin "2") (pinfunction "2_2") (pintype "passive"))
      (node (ref "C23") (pin "2") (pinfunction "2_2") (pintype "passive"))
      (node (ref "C24") (pin "2") (pinfunction "2_2") (pintype "passive"))
      (node (ref "CN1") (pin "GND") (pinfunction "GND_GND") (pintype "power_in"))
      (node (ref "CN1") (pin "GNDBREAK") (pinfunction "GNDBREAK_GNDBREAK") (pintype "power_in"))
      (node (ref "IC1") (pin "11") (pinfunction "GNDINT_11") (pintype "power_in"))
      (node (ref "IC1") (pin "65") (pinfunction "GNDINT_65") (pintype "power_in"))
      (node (ref "IC2") (pin "1") (pinfunction "ADJ_1") (pintype "input"))
      (node (ref "J4") (pin "10") (pinfunction "10_10") (pintype "passive"))
      (node (ref "J4") (pin "2") (pinfunction "2_2") (pintype "passive"))
      (node (ref "J5") (pin "G-") (pinfunction "G-_G-") (pintype "bidirectional"))
      (node (ref "J5") (pin "GND") (pinfunction "GND_GND") (pintype "bidirectional"))
      (node (ref "J5") (pin "SHIELD0") (pinfunction "SHIELD0_SHIELD0") (pintype "bidirectional"))
      (node (ref "J5") (pin "SHIELD1") (pinfunction "SHIELD1_SHIELD1") (pintype "bidirectional"))
      (node (ref "J5") (pin "Y-") (pinfunction "Y-_Y-") (pintype "bidirectional"))
      (node (ref "J6") (pin "1") (pinfunction "1_1") (pintype "passive"))
      (node (ref "J7") (pin "11") (pinfunction "LKT_GND_11") (pintype "power_in"))
      (node (ref "J8") (pin "1") (pinfunction "1_1") (pintype "passive"))
      (node (ref "J9") (pin "16") (pinfunction "16_16") (pintype "passive"))
      (node (ref "L5") (pin "2") (pinfunction "2_2") (pintype "passive"))
      (node (ref "OS1") (pin "2") (pinfunction "VSS_2") (pintype "power_in"))
      (node (ref "OS2") (pin "2") (pinfunction "VSS_2") (pintype "power_in"))
      (node (ref "R110") (pin "2") (pinfunction "2_2") (pintype "passive"))
      (node (ref "R111") (pin "2") (pinfunction "2_2") (pintype "passive"))
      (node (ref "R99") (pin "2") (pinfunction "2_2") (pintype "passive"))
      (node (ref "USB-A") (pin "4") (pinfunction "4_4") (pintype "passive"))
    )
    (net (code "57") (name "I2S_BCLK") (class "Default")
      (node (ref "IC1") (pin "14") (pinfunction "IOB1-14/GCLK1_14") (pintype "bidirectional"))
      (node (ref "J7") (pin "16") (pinfunction "I2S_CLK_16") (pintype "bidirectional"))
      (node (ref "J8") (pin "4") (pinfunction "4_4") (pintype "passive"))
    )
    (net (code "58") (name "I2S_DATA") (class "Default")
      (node (ref "IC1") (pin "16") (pinfunction "IOB1-16_16") (pintype "bidirectional"))
      (node (ref "J7") (pin "18") (pinfunction "I2S_OUT_18") (pintype "bidirectional"))
      (node (ref "J8") (pin "5") (pinfunction "5_5") (pintype "passive"))
    )
    (net (code "59") (name "I2S_LRCLK") (class "Default")
      (node (ref "IC1") (pin "15") (pinfunction "IOB1-15_15") (pintype "bidirectional"))
      (node (ref "J7") (pin "15") (pinfunction "I2S_WS_15") (pintype "bidirectional"))
      (node (ref "J8") (pin "3") (pinfunction "3_3") (pintype "passive"))
    )
    (net (code "60") (name "I2S_MCLK") (class "Default")
      (node (ref "IC1") (pin "12") (pinfunction "IOB1-12/GCLK0_12") (pintype "bidirectional"))
      (node (ref "J8") (pin "2") (pinfunction "2_2") (pintype "passive"))
      (node (ref "R102") (pin "2") (pinfunction "2_2") (pintype "passive"))
      (node (ref "R103") (pin "2") (pinfunction "2_2") (pintype "passive"))
    )
    (net (code "61") (name "LED_LAN") (class "Default")
      (node (ref "J7") (pin "2") (pinfunction "LED_LAN_2") (pintype "bidirectional"))
    )
    (net (code "62") (name "LED_WLAN") (class "Default")
      (node (ref "J7") (pin "20") (pinfunction "LED_WLAN_20") (pintype "bidirectional"))
    )
    (net (code "63") (name "MCLK1_CTL") (class "Default")
      (node (ref "J7") (pin "21") (pinfunction "GPIO_46_21") (pintype "bidirectional"))
      (node (ref "R104") (pin "2") (pinfunction "2_2") (pintype "passive"))
    )
    (net (code "64") (name "MCLK2_CTL") (class "Default")
      (node (ref "J7") (pin "22") (pinfunction "GPIO_45_22") (pintype "bidirectional"))
      (node (ref "R105") (pin "2") (pinfunction "2_2") (pintype "passive"))
    )
    (net (code "65") (name "N$62") (class "Default")
      (node (ref "IC1") (pin "21") (pinfunction "IOB1-21_21") (pintype "bidirectional"))
    )
    (net (code "66") (name "N$63") (class "Default")
      (node (ref "IC1") (pin "20") (pinfunction "IOB1-20_20") (pintype "bidirectional"))
    )
    (net (code "67") (name "N$82") (class "Default")
      (node (ref "IC1") (pin "17") (pinfunction "IOB1-17_17") (pintype "bidirectional"))
    )
    (net (code "68") (name "Net-(C1--)") (class "Default")
      (node (ref "C1") (pin "2") (pinfunction "-_2") (pintype "passive"))
      (node (ref "C2") (pin "2") (pinfunction "2_2") (pintype "passive"))
      (node (ref "R100") (pin "1") (pinfunction "1_1") (pintype "passive"))
    )
    (net (code "69") (name "Net-(C11--)") (class "Default")
      (node (ref "C11") (pin "2") (pinfunction "-_2") (pintype "passive"))
      (node (ref "C12") (pin "2") (pinfunction "2_2") (pintype "passive"))
      (node (ref "R101") (pin "1") (pinfunction "1_1") (pintype "passive"))
    )
    (net (code "70") (name "Net-(C21-Pad1)") (class "Default")
      (node (ref "C21") (pin "1") (pinfunction "1_1") (pintype "passive"))
      (node (ref "J5") (pin "P5") (pinfunction "P5_P5") (pintype "bidirectional"))
    )
    (net (code "71") (name "Net-(C22-Pad1)") (class "Default")
      (node (ref "C22") (pin "1") (pinfunction "1_1") (pintype "passive"))
      (node (ref "J5") (pin "P4") (pinfunction "P4_P4") (pintype "bidirectional"))
    )
    (net (code "72") (name "Net-(IC1C-OPTGND-Pad37)") (class "Default")
      (node (ref "IC1") (pin "37") (pinfunction "OPTGND_37") (pintype "power_in"))
      (node (ref "R110") (pin "1") (pinfunction "1_1") (pintype "passive"))
    )
    (net (code "73") (name "Net-(IC1C-OPTGND-Pad90)") (class "Default")
      (node (ref "IC1") (pin "90") (pinfunction "OPTGND_90") (pintype "power_in"))
      (node (ref "R111") (pin "1") (pinfunction "1_1") (pintype "passive"))
    )
    (net (code "74") (name "Net-(IC1C-OPTVCC-Pad39)") (class "Default")
      (node (ref "IC1") (pin "39") (pinfunction "OPTVCC_39") (pintype "power_in"))
      (node (ref "R108") (pin "1") (pinfunction "1_1") (pintype "passive"))
    )
    (net (code "75") (name "Net-(IC1C-OPTVCC-Pad88)") (class "Default")
      (node (ref "IC1") (pin "88") (pinfunction "OPTVCC_88") (pintype "power_in"))
      (node (ref "R109") (pin "1") (pinfunction "1_1") (pintype "passive"))
    )
    (net (code "76") (name "Net-(J5-PadG+)") (class "Default")
      (node (ref "J5") (pin "G+") (pinfunction "G+_G+") (pintype "bidirectional"))
      (node (ref "R107") (pin "2") (pinfunction "2_2") (pintype "passive"))
    )
    (net (code "77") (name "Net-(J5-PadY+)") (class "Default")
      (node (ref "J5") (pin "Y+") (pinfunction "Y+_Y+") (pintype "bidirectional"))
      (node (ref "R106") (pin "2") (pinfunction "2_2") (pintype "passive"))
    )
    (net (code "78") (name "Net-(OS1-CON)") (class "Default")
      (node (ref "OS1") (pin "1") (pinfunction "CON_1") (pintype "input"))
      (node (ref "R104") (pin "1") (pinfunction "1_1") (pintype "passive"))
    )
    (net (code "79") (name "Net-(OS1-OUT)") (class "Default")
      (node (ref "OS1") (pin "3") (pinfunction "OUT_3") (pintype "output"))
      (node (ref "R102") (pin "1") (pinfunction "1_1") (pintype "passive"))
    )
    (net (code "80") (name "Net-(OS1-VDD)") (class "Default")
      (node (ref "C23") (pin "1") (pinfunction "1_1") (pintype "passive"))
      (node (ref "L1") (pin "2") (pinfunction "2_2") (pintype "passive"))
      (node (ref "OS1") (pin "4") (pinfunction "VDD_4") (pintype "power_in"))
    )
    (net (code "81") (name "Net-(OS2-CON)") (class "Default")
      (node (ref "OS2") (pin "1") (pinfunction "CON_1") (pintype "input"))
      (node (ref "R105") (pin "1") (pinfunction "1_1") (pintype "passive"))
    )
    (net (code "82") (name "Net-(OS2-OUT)") (class "Default")
      (node (ref "OS2") (pin "3") (pinfunction "OUT_3") (pintype "output"))
      (node (ref "R103") (pin "1") (pinfunction "1_1") (pintype "passive"))
    )
    (net (code "83") (name "Net-(OS2-VDD)") (class "Default")
      (node (ref "C24") (pin "1") (pinfunction "1_1") (pintype "passive"))
      (node (ref "L2") (pin "2") (pinfunction "2_2") (pintype "passive"))
      (node (ref "OS2") (pin "4") (pinfunction "VDD_4") (pintype "power_in"))
    )
    (net (code "84") (name "Net-(R2-Pad1)") (class "Default")
      (node (ref "R2") (pin "1") (pinfunction "1_1") (pintype "passive"))
      (node (ref "R3") (pin "2") (pinfunction "2_2") (pintype "passive"))
      (node (ref "R4") (pin "2") (pinfunction "2_2") (pintype "passive"))
    )
    (net (code "85") (name "Net-(R3-Pad1)") (class "Default")
      (node (ref "R3") (pin "1") (pinfunction "1_1") (pintype "passive"))
      (node (ref "R5") (pin "2") (pinfunction "2_2") (pintype "passive"))
      (node (ref "R6") (pin "2") (pinfunction "2_2") (pintype "passive"))
    )
    (net (code "86") (name "Net-(R6-Pad1)") (class "Default")
      (node (ref "R6") (pin "1") (pinfunction "1_1") (pintype "passive"))
      (node (ref "R7") (pin "2") (pinfunction "2_2") (pintype "passive"))
      (node (ref "R8") (pin "2") (pinfunction "2_2") (pintype "passive"))
    )
    (net (code "87") (name "Net-(R10-Pad1)") (class "Default")
      (node (ref "R10") (pin "1") (pinfunction "1_1") (pintype "passive"))
      (node (ref "R11") (pin "2") (pinfunction "2_2") (pintype "passive"))
      (node (ref "R12") (pin "2") (pinfunction "2_2") (pintype "passive"))
    )
    (net (code "88") (name "Net-(R10-Pad2)") (class "Default")
      (node (ref "R10") (pin "2") (pinfunction "2_2") (pintype "passive"))
      (node (ref "R7") (pin "1") (pinfunction "1_1") (pintype "passive"))
      (node (ref "R9") (pin "2") (pinfunction "2_2") (pintype "passive"))
    )
    (net (code "89") (name "Net-(R11-Pad1)") (class "Default")
      (node (ref "R11") (pin "1") (pinfunction "1_1") (pintype "passive"))
      (node (ref "R13") (pin "2") (pinfunction "2_2") (pintype "passive"))
      (node (ref "R14") (pin "2") (pinfunction "2_2") (pintype "passive"))
    )
    (net (code "90") (name "Net-(R14-Pad1)") (class "Default")
      (node (ref "R14") (pin "1") (pinfunction "1_1") (pintype "passive"))
      (node (ref "R15") (pin "2") (pinfunction "2_2") (pintype "passive"))
      (node (ref "R16") (pin "2") (pinfunction "2_2") (pintype "passive"))
    )
    (net (code "91") (name "Net-(R15-Pad1)") (class "Default")
      (node (ref "R15") (pin "1") (pinfunction "1_1") (pintype "passive"))
      (node (ref "R17") (pin "2") (pinfunction "2_2") (pintype "passive"))
      (node (ref "R18") (pin "2") (pinfunction "2_2") (pintype "passive"))
    )
    (net (code "92") (name "Net-(R18-Pad1)") (class "Default")
      (node (ref "R18") (pin "1") (pinfunction "1_1") (pintype "passive"))
      (node (ref "R19") (pin "2") (pinfunction "2_2") (pintype "passive"))
      (node (ref "R20") (pin "2") (pinfunction "2_2") (pintype "passive"))
    )
    (net (code "93") (name "Net-(R19-Pad1)") (class "Default")
      (node (ref "R19") (pin "1") (pinfunction "1_1") (pintype "passive"))
      (node (ref "R21") (pin "2") (pinfunction "2_2") (pintype "passive"))
      (node (ref "R22") (pin "2") (pinfunction "2_2") (pintype "passive"))
    )
    (net (code "94") (name "Net-(R22-Pad1)") (class "Default")
      (node (ref "R22") (pin "1") (pinfunction "1_1") (pintype "passive"))
      (node (ref "R23") (pin "2") (pinfunction "2_2") (pintype "passive"))
      (node (ref "R24") (pin "2") (pinfunction "2_2") (pintype "passive"))
    )
    (net (code "95") (name "Net-(R23-Pad1)") (class "Default")
      (node (ref "R23") (pin "1") (pinfunction "1_1") (pintype "passive"))
      (node (ref "R25") (pin "2") (pinfunction "2_2") (pintype "passive"))
      (node (ref "R26") (pin "2") (pinfunction "2_2") (pintype "passive"))
    )
    (net (code "96") (name "Net-(R26-Pad1)") (class "Default")
      (node (ref "R26") (pin "1") (pinfunction "1_1") (pintype "passive"))
      (node (ref "R27") (pin "2") (pinfunction "2_2") (pintype "passive"))
      (node (ref "R28") (pin "2") (pinfunction "2_2") (pintype "passive"))
    )
    (net (code "97") (name "Net-(R27-Pad1)") (class "Default")
      (node (ref "R27") (pin "1") (pinfunction "1_1") (pintype "passive"))
      (node (ref "R29") (pin "2") (pinfunction "2_2") (pintype "passive"))
      (node (ref "R30") (pin "2") (pinfunction "2_2") (pintype "passive"))
    )
    (net (code "98") (name "Net-(R30-Pad1)") (class "Default")
      (node (ref "R30") (pin "1") (pinfunction "1_1") (pintype "passive"))
      (node (ref "R31") (pin "2") (pinfunction "2_2") (pintype "passive"))
      (node (ref "R32") (pin "2") (pinfunction "2_2") (pintype "passive"))
    )
    (net (code "99") (name "Net-(R31-Pad1)") (class "Default")
      (node (ref "R31") (pin "1") (pinfunction "1_1") (pintype "passive"))
      (node (ref "R33") (pin "2") (pinfunction "2_2") (pintype "passive"))
      (node (ref "R34") (pin "2") (pinfunction "2_2") (pintype "passive"))
    )
    (net (code "100") (name "Net-(R34-Pad1)") (class "Default")
      (node (ref "R34") (pin "1") (pinfunction "1_1") (pintype "passive"))
      (node (ref "R35") (pin "2") (pinfunction "2_2") (pintype "passive"))
      (node (ref "R36") (pin "2") (pinfunction "2_2") (pintype "passive"))
    )
    (net (code "101") (name "Net-(R35-Pad1)") (class "Default")
      (node (ref "R35") (pin "1") (pinfunction "1_1") (pintype "passive"))
      (node (ref "R37") (pin "2") (pinfunction "2_2") (pintype "passive"))
      (node (ref "R38") (pin "2") (pinfunction "2_2") (pintype "passive"))
    )
    (net (code "102") (name "Net-(R38-Pad1)") (class "Default")
      (node (ref "R38") (pin "1") (pinfunction "1_1") (pintype "passive"))
      (node (ref "R39") (pin "2") (pinfunction "2_2") (pintype "passive"))
      (node (ref "R40") (pin "2") (pinfunction "2_2") (pintype "passive"))
    )
    (net (code "103") (name "Net-(R39-Pad1)") (class "Default")
      (node (ref "R39") (pin "1") (pinfunction "1_1") (pintype "passive"))
      (node (ref "R41") (pin "2") (pinfunction "2_2") (pintype "passive"))
      (node (ref "R42") (pin "2") (pinfunction "2_2") (pintype "passive"))
    )
    (net (code "104") (name "Net-(R42-Pad1)") (class "Default")
      (node (ref "R42") (pin "1") (pinfunction "1_1") (pintype "passive"))
      (node (ref "R43") (pin "2") (pinfunction "2_2") (pintype "passive"))
      (node (ref "R44") (pin "2") (pinfunction "2_2") (pintype "passive"))
    )
    (net (code "105") (name "Net-(R43-Pad1)") (class "Default")
      (node (ref "R43") (pin "1") (pinfunction "1_1") (pintype "passive"))
      (node (ref "R45") (pin "2") (pinfunction "2_2") (pintype "passive"))
      (node (ref "R46") (pin "2") (pinfunction "2_2") (pintype "passive"))
    )
    (net (code "106") (name "Net-(R46-Pad1)") (class "Default")
      (node (ref "R46") (pin "1") (pinfunction "1_1") (pintype "passive"))
      (node (ref "R47") (pin "2") (pinfunction "2_2") (pintype "passive"))
      (node (ref "R48") (pin "2") (pinfunction "2_2") (pintype "passive"))
    )
    (net (code "107") (name "Net-(R50-Pad1)") (class "Default")
      (node (ref "R50") (pin "1") (pinfunction "1_1") (pintype "passive"))
      (node (ref "R51") (pin "2") (pinfunction "2_2") (pintype "passive"))
      (node (ref "R52") (pin "2") (pinfunction "2_2") (pintype "passive"))
    )
    (net (code "108") (name "Net-(R51-Pad1)") (class "Default")
      (node (ref "R51") (pin "1") (pinfunction "1_1") (pintype "passive"))
      (node (ref "R53") (pin "2") (pinfunction "2_2") (pintype "passive"))
      (node (ref "R54") (pin "2") (pinfunction "2_2") (pintype "passive"))
    )
    (net (code "109") (name "Net-(R54-Pad1)") (class "Default")
      (node (ref "R54") (pin "1") (pinfunction "1_1") (pintype "passive"))
      (node (ref "R55") (pin "2") (pinfunction "2_2") (pintype "passive"))
      (node (ref "R56") (pin "2") (pinfunction "2_2") (pintype "passive"))
    )
    (net (code "110") (name "Net-(R55-Pad1)") (class "Default")
      (node (ref "R55") (pin "1") (pinfunction "1_1") (pintype "passive"))
      (node (ref "R57") (pin "2") (pinfunction "2_2") (pintype "passive"))
      (node (ref "R58") (pin "2") (pinfunction "2_2") (pintype "passive"))
    )
    (net (code "111") (name "Net-(R58-Pad1)") (class "Default")
      (node (ref "R58") (pin "1") (pinfunction "1_1") (pintype "passive"))
      (node (ref "R59") (pin "2") (pinfunction "2_2") (pintype "passive"))
      (node (ref "R60") (pin "2") (pinfunction "2_2") (pintype "passive"))
    )
    (net (code "112") (name "Net-(R59-Pad1)") (class "Default")
      (node (ref "R59") (pin "1") (pinfunction "1_1") (pintype "passive"))
      (node (ref "R61") (pin "2") (pinfunction "2_2") (pintype "passive"))
      (node (ref "R62") (pin "2") (pinfunction "2_2") (pintype "passive"))
    )
    (net (code "113") (name "Net-(R62-Pad1)") (class "Default")
      (node (ref "R62") (pin "1") (pinfunction "1_1") (pintype "passive"))
      (node (ref "R63") (pin "2") (pinfunction "2_2") (pintype "passive"))
      (node (ref "R64") (pin "2") (pinfunction "2_2") (pintype "passive"))
    )
    (net (code "114") (name "Net-(R63-Pad1)") (class "Default")
      (node (ref "R63") (pin "1") (pinfunction "1_1") (pintype "passive"))
      (node (ref "R65") (pin "2") (pinfunction "2_2") (pintype "passive"))
      (node (ref "R66") (pin "2") (pinfunction "2_2") (pintype "passive"))
    )
    (net (code "115") (name "Net-(R66-Pad1)") (class "Default")
      (node (ref "R66") (pin "1") (pinfunction "1_1") (pintype "passive"))
      (node (ref "R67") (pin "2") (pinfunction "2_2") (pintype "passive"))
      (node (ref "R68") (pin "2") (pinfunction "2_2") (pintype "passive"))
    )
    (net (code "116") (name "Net-(R67-Pad1)") (class "Default")
      (node (ref "R67") (pin "1") (pinfunction "1_1") (pintype "passive"))
      (node (ref "R69") (pin "2") (pinfunction "2_2") (pintype "passive"))
      (node (ref "R70") (pin "2") (pinfunction "2_2") (pintype "passive"))
    )
    (net (code "117") (name "Net-(R70-Pad1)") (class "Default")
      (node (ref "R70") (pin "1") (pinfunction "1_1") (pintype "passive"))
      (node (ref "R71") (pin "2") (pinfunction "2_2") (pintype "passive"))
      (node (ref "R72") (pin "2") (pinfunction "2_2") (pintype "passive"))
    )
    (net (code "118") (name "Net-(R71-Pad1)") (class "Default")
      (node (ref "R71") (pin "1") (pinfunction "1_1") (pintype "passive"))
      (node (ref "R73") (pin "2") (pinfunction "2_2") (pintype "passive"))
      (node (ref "R74") (pin "2") (pinfunction "2_2") (pintype "passive"))
    )
    (net (code "119") (name "Net-(R74-Pad1)") (class "Default")
      (node (ref "R74") (pin "1") (pinfunction "1_1") (pintype "passive"))
      (node (ref "R75") (pin "2") (pinfunction "2_2") (pintype "passive"))
      (node (ref "R76") (pin "2") (pinfunction "2_2") (pintype "passive"))
    )
    (net (code "120") (name "Net-(R75-Pad1)") (class "Default")
      (node (ref "R75") (pin "1") (pinfunction "1_1") (pintype "passive"))
      (node (ref "R77") (pin "2") (pinfunction "2_2") (pintype "passive"))
      (node (ref "R78") (pin "2") (pinfunction "2_2") (pintype "passive"))
    )
    (net (code "121") (name "Net-(R78-Pad1)") (class "Default")
      (node (ref "R78") (pin "1") (pinfunction "1_1") (pintype "passive"))
      (node (ref "R79") (pin "2") (pinfunction "2_2") (pintype "passive"))
      (node (ref "R80") (pin "2") (pinfunction "2_2") (pintype "passive"))
    )
    (net (code "122") (name "Net-(R79-Pad1)") (class "Default")
      (node (ref "R79") (pin "1") (pinfunction "1_1") (pintype "passive"))
      (node (ref "R81") (pin "2") (pinfunction "2_2") (pintype "passive"))
      (node (ref "R82") (pin "2") (pinfunction "2_2") (pintype "passive"))
    )
    (net (code "123") (name "Net-(R82-Pad1)") (class "Default")
      (node (ref "R82") (pin "1") (pinfunction "1_1") (pintype "passive"))
      (node (ref "R83") (pin "2") (pinfunction "2_2") (pintype "passive"))
      (node (ref "R84") (pin "2") (pinfunction "2_2") (pintype "passive"))
    )
    (net (code "124") (name "Net-(R83-Pad1)") (class "Default")
      (node (ref "R83") (pin "1") (pinfunction "1_1") (pintype "passive"))
      (node (ref "R85") (pin "2") (pinfunction "2_2") (pintype "passive"))
      (node (ref "R86") (pin "2") (pinfunction "2_2") (pintype "passive"))
    )
    (net (code "125") (name "Net-(R86-Pad1)") (class "Default")
      (node (ref "R86") (pin "1") (pinfunction "1_1") (pintype "passive"))
      (node (ref "R87") (pin "2") (pinfunction "2_2") (pintype "passive"))
      (node (ref "R88") (pin "2") (pinfunction "2_2") (pintype "passive"))
    )
    (net (code "126") (name "Net-(R87-Pad1)") (class "Default")
      (node (ref "R87") (pin "1") (pinfunction "1_1") (pintype "passive"))
      (node (ref "R89") (pin "2") (pinfunction "2_2") (pintype "passive"))
      (node (ref "R90") (pin "2") (pinfunction "2_2") (pintype "passive"))
    )
    (net (code "127") (name "Net-(R90-Pad1)") (class "Default")
      (node (ref "R90") (pin "1") (pinfunction "1_1") (pintype "passive"))
      (node (ref "R91") (pin "2") (pinfunction "2_2") (pintype "passive"))
      (node (ref "R92") (pin "2") (pinfunction "2_2") (pintype "passive"))
    )
    (net (code "128") (name "Net-(R91-Pad1)") (class "Default")
      (node (ref "R91") (pin "1") (pinfunction "1_1") (pintype "passive"))
      (node (ref "R93") (pin "2") (pinfunction "2_2") (pintype "passive"))
      (node (ref "R94") (pin "2") (pinfunction "2_2") (pintype "passive"))
    )
    (net (code "129") (name "Net-(R94-Pad1)") (class "Default")
      (node (ref "R94") (pin "1") (pinfunction "1_1") (pintype "passive"))
      (node (ref "R95") (pin "2") (pinfunction "2_2") (pintype "passive"))
      (node (ref "R96") (pin "2") (pinfunction "2_2") (pintype "passive"))
    )
    (net (code "130") (name "R2R_AC_L") (class "Default")
      (node (ref "C10") (pin "1") (pinfunction "1_1") (pintype "passive"))
      (node (ref "C9") (pin "1") (pinfunction "1_1") (pintype "passive"))
      (node (ref "J3") (pin "TIP") (pinfunction "LEFT_TIP") (pintype "bidirectional"))
      (node (ref "R100") (pin "2") (pinfunction "2_2") (pintype "passive"))
    )
    (net (code "131") (name "R2R_AC_R") (class "Default")
      (node (ref "C13") (pin "1") (pinfunction "1_1") (pintype "passive"))
      (node (ref "C14") (pin "1") (pinfunction "1_1") (pintype "passive"))
      (node (ref "J3") (pin "RING") (pinfunction "RIGHT_RING") (pintype "bidirectional"))
      (node (ref "R101") (pin "2") (pinfunction "2_2") (pintype "passive"))
    )
    (net (code "132") (name "R2R_DC_L") (class "Default")
      (node (ref "C1") (pin "1") (pinfunction "+_1") (pintype "passive"))
      (node (ref "C2") (pin "1") (pinfunction "1_1") (pintype "passive"))
      (node (ref "R1") (pin "2") (pinfunction "2_2") (pintype "passive"))
      (node (ref "R2") (pin "2") (pinfunction "2_2") (pintype "passive"))
    )
    (net (code "133") (name "R2R_DC_R") (class "Default")
      (node (ref "C11") (pin "1") (pinfunction "+_1") (pintype "passive"))
      (node (ref "C12") (pin "1") (pinfunction "1_1") (pintype "passive"))
      (node (ref "R49") (pin "2") (pinfunction "2_2") (pintype "passive"))
      (node (ref "R50") (pin "2") (pinfunction "2_2") (pintype "passive"))
    )
    (net (code "134") (name "RAW_01") (class "Default")
      (node (ref "IC1") (pin "2") (pinfunction "IOB1-2_2") (pintype "bidirectional"))
      (node (ref "J9") (pin "1") (pinfunction "1_1") (pintype "passive"))
    )
    (net (code "135") (name "RAW_02") (class "Default")
      (node (ref "IC1") (pin "3") (pinfunction "IOB1-3_3") (pintype "bidirectional"))
      (node (ref "J9") (pin "2") (pinfunction "2_2") (pintype "passive"))
    )
    (net (code "136") (name "RAW_03") (class "Default")
      (node (ref "IC1") (pin "4") (pinfunction "IOB1-4_4") (pintype "bidirectional"))
      (node (ref "J9") (pin "3") (pinfunction "3_3") (pintype "passive"))
    )
    (net (code "137") (name "RAW_04") (class "Default")
      (node (ref "IC1") (pin "5") (pinfunction "IOB1-5_5") (pintype "bidirectional"))
      (node (ref "J9") (pin "4") (pinfunction "4_4") (pintype "passive"))
    )
    (net (code "138") (name "RAW_05") (class "Default")
      (node (ref "IC1") (pin "6") (pinfunction "IOB1-6_6") (pintype "bidirectional"))
      (node (ref "J9") (pin "5") (pinfunction "5_5") (pintype "passive"))
    )
    (net (code "139") (name "RAW_06") (class "Default")
      (node (ref "IC1") (pin "7") (pinfunction "IOB1-7_7") (pintype "bidirectional"))
      (node (ref "J9") (pin "6") (pinfunction "6_6") (pintype "passive"))
    )
    (net (code "140") (name "RAW_07") (class "Default")
      (node (ref "IC1") (pin "69") (pinfunction "IOB2-69_69") (pintype "bidirectional"))
      (node (ref "J9") (pin "7") (pinfunction "7_7") (pintype "passive"))
    )
    (net (code "141") (name "RAW_08") (class "Default")
      (node (ref "IC1") (pin "68") (pinfunction "IOB2-68_68") (pintype "bidirectional"))
      (node (ref "J9") (pin "8") (pinfunction "8_8") (pintype "passive"))
    )
    (net (code "142") (name "RAW_09") (class "Default")
      (node (ref "IC1") (pin "67") (pinfunction "IOB2-67_67") (pintype "bidirectional"))
      (node (ref "J9") (pin "9") (pinfunction "9_9") (pintype "passive"))
    )
    (net (code "143") (name "RAW_10") (class "Default")
      (node (ref "IC1") (pin "66") (pinfunction "IOB2-66_66") (pintype "bidirectional"))
      (node (ref "J9") (pin "10") (pinfunction "10_10") (pintype "passive"))
    )
    (net (code "144") (name "RAW_11") (class "Default")
      (node (ref "IC1") (pin "64") (pinfunction "IOB2-64/GCLK3_64") (pintype "bidirectional"))
      (node (ref "J9") (pin "11") (pinfunction "11_11") (pintype "passive"))
    )
    (net (code "145") (name "RAW_12") (class "Default")
      (node (ref "IC1") (pin "62") (pinfunction "IOB2-62/GCLK2_62") (pintype "bidirectional"))
      (node (ref "J9") (pin "12") (pinfunction "12_12") (pintype "passive"))
    )
    (net (code "146") (name "RAW_13") (class "Default")
      (node (ref "IC1") (pin "61") (pinfunction "IOB2-61_61") (pintype "bidirectional"))
      (node (ref "J9") (pin "13") (pinfunction "13_13") (pintype "passive"))
    )
    (net (code "147") (name "RAW_14") (class "Default")
      (node (ref "IC1") (pin "58") (pinfunction "IOB2-58_58") (pintype "bidirectional"))
      (node (ref "J9") (pin "14") (pinfunction "14_14") (pintype "passive"))
    )
    (net (code "148") (name "RAW_15") (class "Default")
      (node (ref "IC1") (pin "57") (pinfunction "IOB2-57_57") (pintype "bidirectional"))
      (node (ref "J9") (pin "15") (pinfunction "15_15") (pintype "passive"))
    )
    (net (code "149") (name "TCK") (class "Default")
      (node (ref "IC1") (pin "24") (pinfunction "TCK_24") (pintype "input"))
      (node (ref "J4") (pin "1") (pinfunction "1_1") (pintype "passive"))
      (node (ref "R99") (pin "1") (pinfunction "1_1") (pintype "passive"))
    )
    (net (code "150") (name "TDI") (class "Default")
      (node (ref "IC1") (pin "23") (pinfunction "TDI_23") (pintype "input"))
      (node (ref "J4") (pin "9") (pinfunction "9_9") (pintype "passive"))
      (node (ref "R98") (pin "2") (pinfunction "2_2") (pintype "passive"))
    )
    (net (code "151") (name "TDO") (class "Default")
      (node (ref "IC1") (pin "25") (pinfunction "TDO_25") (pintype "output"))
      (node (ref "J4") (pin "3") (pinfunction "3_3") (pintype "passive"))
    )
    (net (code "152") (name "TMS") (class "Default")
      (node (ref "IC1") (pin "22") (pinfunction "TMS_22") (pintype "input"))
      (node (ref "J4") (pin "5") (pinfunction "5_5") (pintype "passive"))
      (node (ref "R97") (pin "2") (pinfunction "2_2") (pintype "passive"))
    )
    (net (code "153") (name "TP_1") (class "Default")
      (node (ref "R106") (pin "1") (pinfunction "1_1") (pintype "passive"))
      (node (ref "TP1") (pin "TP") (pinfunction "TP_TP") (pintype "input"))
    )
    (net (code "154") (name "TP_2") (class "Default")
      (node (ref "R107") (pin "1") (pinfunction "1_1") (pintype "passive"))
      (node (ref "TP2") (pin "TP") (pinfunction "TP_TP") (pintype "input"))
    )
    (net (code "155") (name "UART_RX") (class "Default")
      (node (ref "J6") (pin "3") (pinfunction "3_3") (pintype "passive"))
      (node (ref "J7") (pin "10") (pinfunction "UART2_RX_10") (pintype "bidirectional"))
    )
    (net (code "156") (name "UART_TX") (class "Default")
      (node (ref "J6") (pin "4") (pinfunction "4_4") (pintype "passive"))
      (node (ref "J7") (pin "9") (pinfunction "UART2_TX_9") (pintype "bidirectional"))
    )
    (net (code "157") (name "USB_D+") (class "Default")
      (node (ref "J7") (pin "7") (pinfunction "USB_DP_7") (pintype "bidirectional"))
      (node (ref "USB-A") (pin "3") (pinfunction "3_3") (pintype "passive"))
    )
    (net (code "158") (name "USB_D-") (class "Default")
      (node (ref "J7") (pin "8") (pinfunction "USB_DM_8") (pintype "bidirectional"))
      (node (ref "USB-A") (pin "2") (pinfunction "2_2") (pintype "passive"))
    )
    (net (code "159") (name "USB_VBUS") (class "Default")
      (node (ref "USB-A") (pin "1") (pinfunction "1_1") (pintype "passive"))
    )
    (net (code "160") (name "VCC") (class "Default")
      (node (ref "C15") (pin "1") (pinfunction "1_1") (pintype "passive"))
      (node (ref "C16") (pin "1") (pinfunction "1_1") (pintype "passive"))
      (node (ref "C18") (pin "1") (pinfunction "1_1") (pintype "passive"))
      (node (ref "C20") (pin "+") (pinfunction "+_+") (pintype "passive"))
      (node (ref "IC1") (pin "13") (pinfunction "VCCINT_13") (pintype "power_in"))
      (node (ref "IC1") (pin "63") (pinfunction "VCCINT_63") (pintype "power_in"))
      (node (ref "J4") (pin "4") (pinfunction "4_4") (pintype "passive"))
      (node (ref "J8") (pin "6") (pinfunction "6_6") (pintype "passive"))
      (node (ref "L1") (pin "1") (pinfunction "1_1") (pintype "passive"))
      (node (ref "L2") (pin "1") (pinfunction "1_1") (pintype "passive"))
      (node (ref "L4") (pin "P$2") (pinfunction "2_P$2") (pintype "passive"))
      (node (ref "R108") (pin "2") (pinfunction "2_2") (pintype "passive"))
      (node (ref "R109") (pin "2") (pinfunction "2_2") (pintype "passive"))
      (node (ref "R97") (pin "1") (pinfunction "1_1") (pintype "passive"))
      (node (ref "R98") (pin "1") (pinfunction "1_1") (pintype "passive"))
    )
    (net (code "161") (name "VCCIO") (class "Default")
      (node (ref "C17") (pin "1") (pinfunction "1_1") (pintype "passive"))
      (node (ref "C19") (pin "+") (pinfunction "+_+") (pintype "passive"))
      (node (ref "C3") (pin "1") (pinfunction "1_1") (pintype "passive"))
      (node (ref "C4") (pin "1") (pinfunction "1_1") (pintype "passive"))
      (node (ref "C5") (pin "1") (pinfunction "1_1") (pintype "passive"))
      (node (ref "C6") (pin "1") (pinfunction "1_1") (pintype "passive"))
      (node (ref "C7") (pin "1") (pinfunction "1_1") (pintype "passive"))
      (node (ref "C8") (pin "1") (pinfunction "1_1") (pintype "passive"))
      (node (ref "IC1") (pin "31") (pinfunction "VCCIO1_31") (pintype "power_in"))
      (node (ref "IC1") (pin "45") (pinfunction "VCCIO1_45") (pintype "power_in"))
      (node (ref "IC1") (pin "59") (pinfunction "VCCIO2_59") (pintype "power_in"))
      (node (ref "IC1") (pin "80") (pinfunction "VCCIO2_80") (pintype "power_in"))
      (node (ref "IC1") (pin "9") (pinfunction "VCCIO1_9") (pintype "power_in"))
      (node (ref "IC1") (pin "94") (pinfunction "VCCIO2_94") (pintype "power_in"))
      (node (ref "L3") (pin "P$2") (pinfunction "2_P$2") (pintype "passive"))
    )
    (net (code "162") (name "unconnected-(IC1A-IOB1-8-Pad8)") (class "Default")
      (node (ref "IC1") (pin "8") (pinfunction "IOB1-8_8") (pintype "bidirectional"))
    )
    (net (code "163") (name "unconnected-(IC1A-IOB1-18-Pad18)") (class "Default")
      (node (ref "IC1") (pin "18") (pinfunction "IOB1-18_18") (pintype "bidirectional"))
    )
    (net (code "164") (name "unconnected-(IC1A-IOB1-19-Pad19)") (class "Default")
      (node (ref "IC1") (pin "19") (pinfunction "IOB1-19_19") (pintype "bidirectional"))
    )
    (net (code "165") (name "unconnected-(IC1B-IOB2-1-Pad1)") (class "Default")
      (node (ref "IC1") (pin "1") (pinfunction "IOB2-1_1") (pintype "bidirectional"))
    )
    (net (code "166") (name "unconnected-(IC1B-IOB2-56-Pad56)") (class "Default")
      (node (ref "IC1") (pin "56") (pinfunction "IOB2-56_56") (pintype "bidirectional"))
    )
    (net (code "167") (name "unconnected-(IC1B-IOB2-70-Pad70)") (class "Default")
      (node (ref "IC1") (pin "70") (pinfunction "IOB2-70_70") (pintype "bidirectional"))
    )
    (net (code "168") (name "unconnected-(J4-Pad6)") (class "Default")
      (node (ref "J4") (pin "6") (pinfunction "6_6") (pintype "passive"))
    )
    (net (code "169") (name "unconnected-(J4-Pad7)") (class "Default")
      (node (ref "J4") (pin "7") (pinfunction "7_7") (pintype "passive"))
    )
    (net (code "170") (name "unconnected-(J4-Pad8)") (class "Default")
      (node (ref "J4") (pin "8") (pinfunction "8_8") (pintype "passive"))
    )
    (net (code "171") (name "unconnected-(J5-PadNC)") (class "Default")
      (node (ref "J5") (pin "NC") (pinfunction "NC_NC") (pintype "bidirectional"))
    )
    (net (code "172") (name "unconnected-(J7-GPIO_12-Pad24)") (class "Default")
      (node (ref "J7") (pin "24") (pinfunction "GPIO_12_24") (pintype "bidirectional"))
    )
    (net (code "173") (name "unconnected-(J7-GPIO_13-Pad23)") (class "Default")
      (node (ref "J7") (pin "23") (pinfunction "GPIO_13_23") (pintype "bidirectional"))
    )
    (net (code "174") (name "unconnected-(J7-GPIO_14-Pad36)") (class "Default")
      (node (ref "J7") (pin "36") (pinfunction "GPIO_14_36") (pintype "bidirectional"))
    )
    (net (code "175") (name "unconnected-(J7-GPIO_15-Pad35)") (class "Default")
      (node (ref "J7") (pin "35") (pinfunction "GPIO_15_35") (pintype "bidirectional"))
    )
    (net (code "176") (name "unconnected-(J7-GPIO_16-Pad34)") (class "Default")
      (node (ref "J7") (pin "34") (pinfunction "GPIO_16_34") (pintype "bidirectional"))
    )
    (net (code "177") (name "unconnected-(J7-GPIO_17-Pad33)") (class "Default")
      (node (ref "J7") (pin "33") (pinfunction "GPIO_17_33") (pintype "bidirectional"))
    )
    (net (code "178") (name "unconnected-(J7-GPIO_18-Pad31)") (class "Default")
      (node (ref "J7") (pin "31") (pinfunction "GPIO_18_31") (pintype "bidirectional"))
    )
    (net (code "179") (name "unconnected-(J7-GPIO_19-Pad32)") (class "Default")
      (node (ref "J7") (pin "32") (pinfunction "GPIO_19_32") (pintype "bidirectional"))
    )
    (net (code "180") (name "unconnected-(J7-GPIO_37-Pad19)") (class "Default")
      (node (ref "J7") (pin "19") (pinfunction "GPIO_37_19") (pintype "bidirectional"))
    )
    (net (code "181") (name "unconnected-(J7-I2C_SDA-Pad25)") (class "Default")
      (node (ref "J7") (pin "25") (pinfunction "I2C_SDA_25") (pintype "bidirectional"))
    )
    (net (code "182") (name "unconnected-(J7-I2C__SCL-Pad26)") (class "Default")
      (node (ref "J7") (pin "26") (pinfunction "I2C__SCL_26") (pintype "bidirectional"))
    )
    (net (code "183") (name "unconnected-(J7-I2S_IN-Pad17)") (class "Default")
      (node (ref "J7") (pin "17") (pinfunction "I2S_IN_17") (pintype "bidirectional"))
    )
    (net (code "184") (name "unconnected-(J7-LKT_3V3-Pad12)") (class "Default")
      (node (ref "J7") (pin "12") (pinfunction "LKT_3V3_12") (pintype "bidirectional"))
    )
    (net (code "185") (name "unconnected-(J7-LKT_VCC-Pad13)") (class "Default")
      (node (ref "J7") (pin "13") (pinfunction "LKT_VCC_13") (pintype "bidirectional"))
    )
    (net (code "186") (name "unconnected-(J7-RST-Pad1)") (class "Default")
      (node (ref "J7") (pin "1") (pinfunction "RST_1") (pintype "bidirectional"))
    )
    (net (code "187") (name "unconnected-(J7-SPI_CLK-Pad29)") (class "Default")
      (node (ref "J7") (pin "29") (pinfunction "SPI_CLK_29") (pintype "bidirectional"))
    )
    (net (code "188") (name "unconnected-(J7-SPI_CS1-Pad30)") (class "Default")
      (node (ref "J7") (pin "30") (pinfunction "SPI_CS1_30") (pintype "bidirectional"))
    )
    (net (code "189") (name "unconnected-(J7-SPI_MISO-Pad28)") (class "Default")
      (node (ref "J7") (pin "28") (pinfunction "SPI_MISO_28") (pintype "bidirectional"))
    )
    (net (code "190") (name "unconnected-(J7-SPI_MOSI-Pad27)") (class "Default")
      (node (ref "J7") (pin "27") (pinfunction "SPI_MOSI_27") (pintype "bidirectional"))
    )
  )
)
